# IoT-Main_Board.net
KiCad netlist of a schematic drawn in EasyEDA
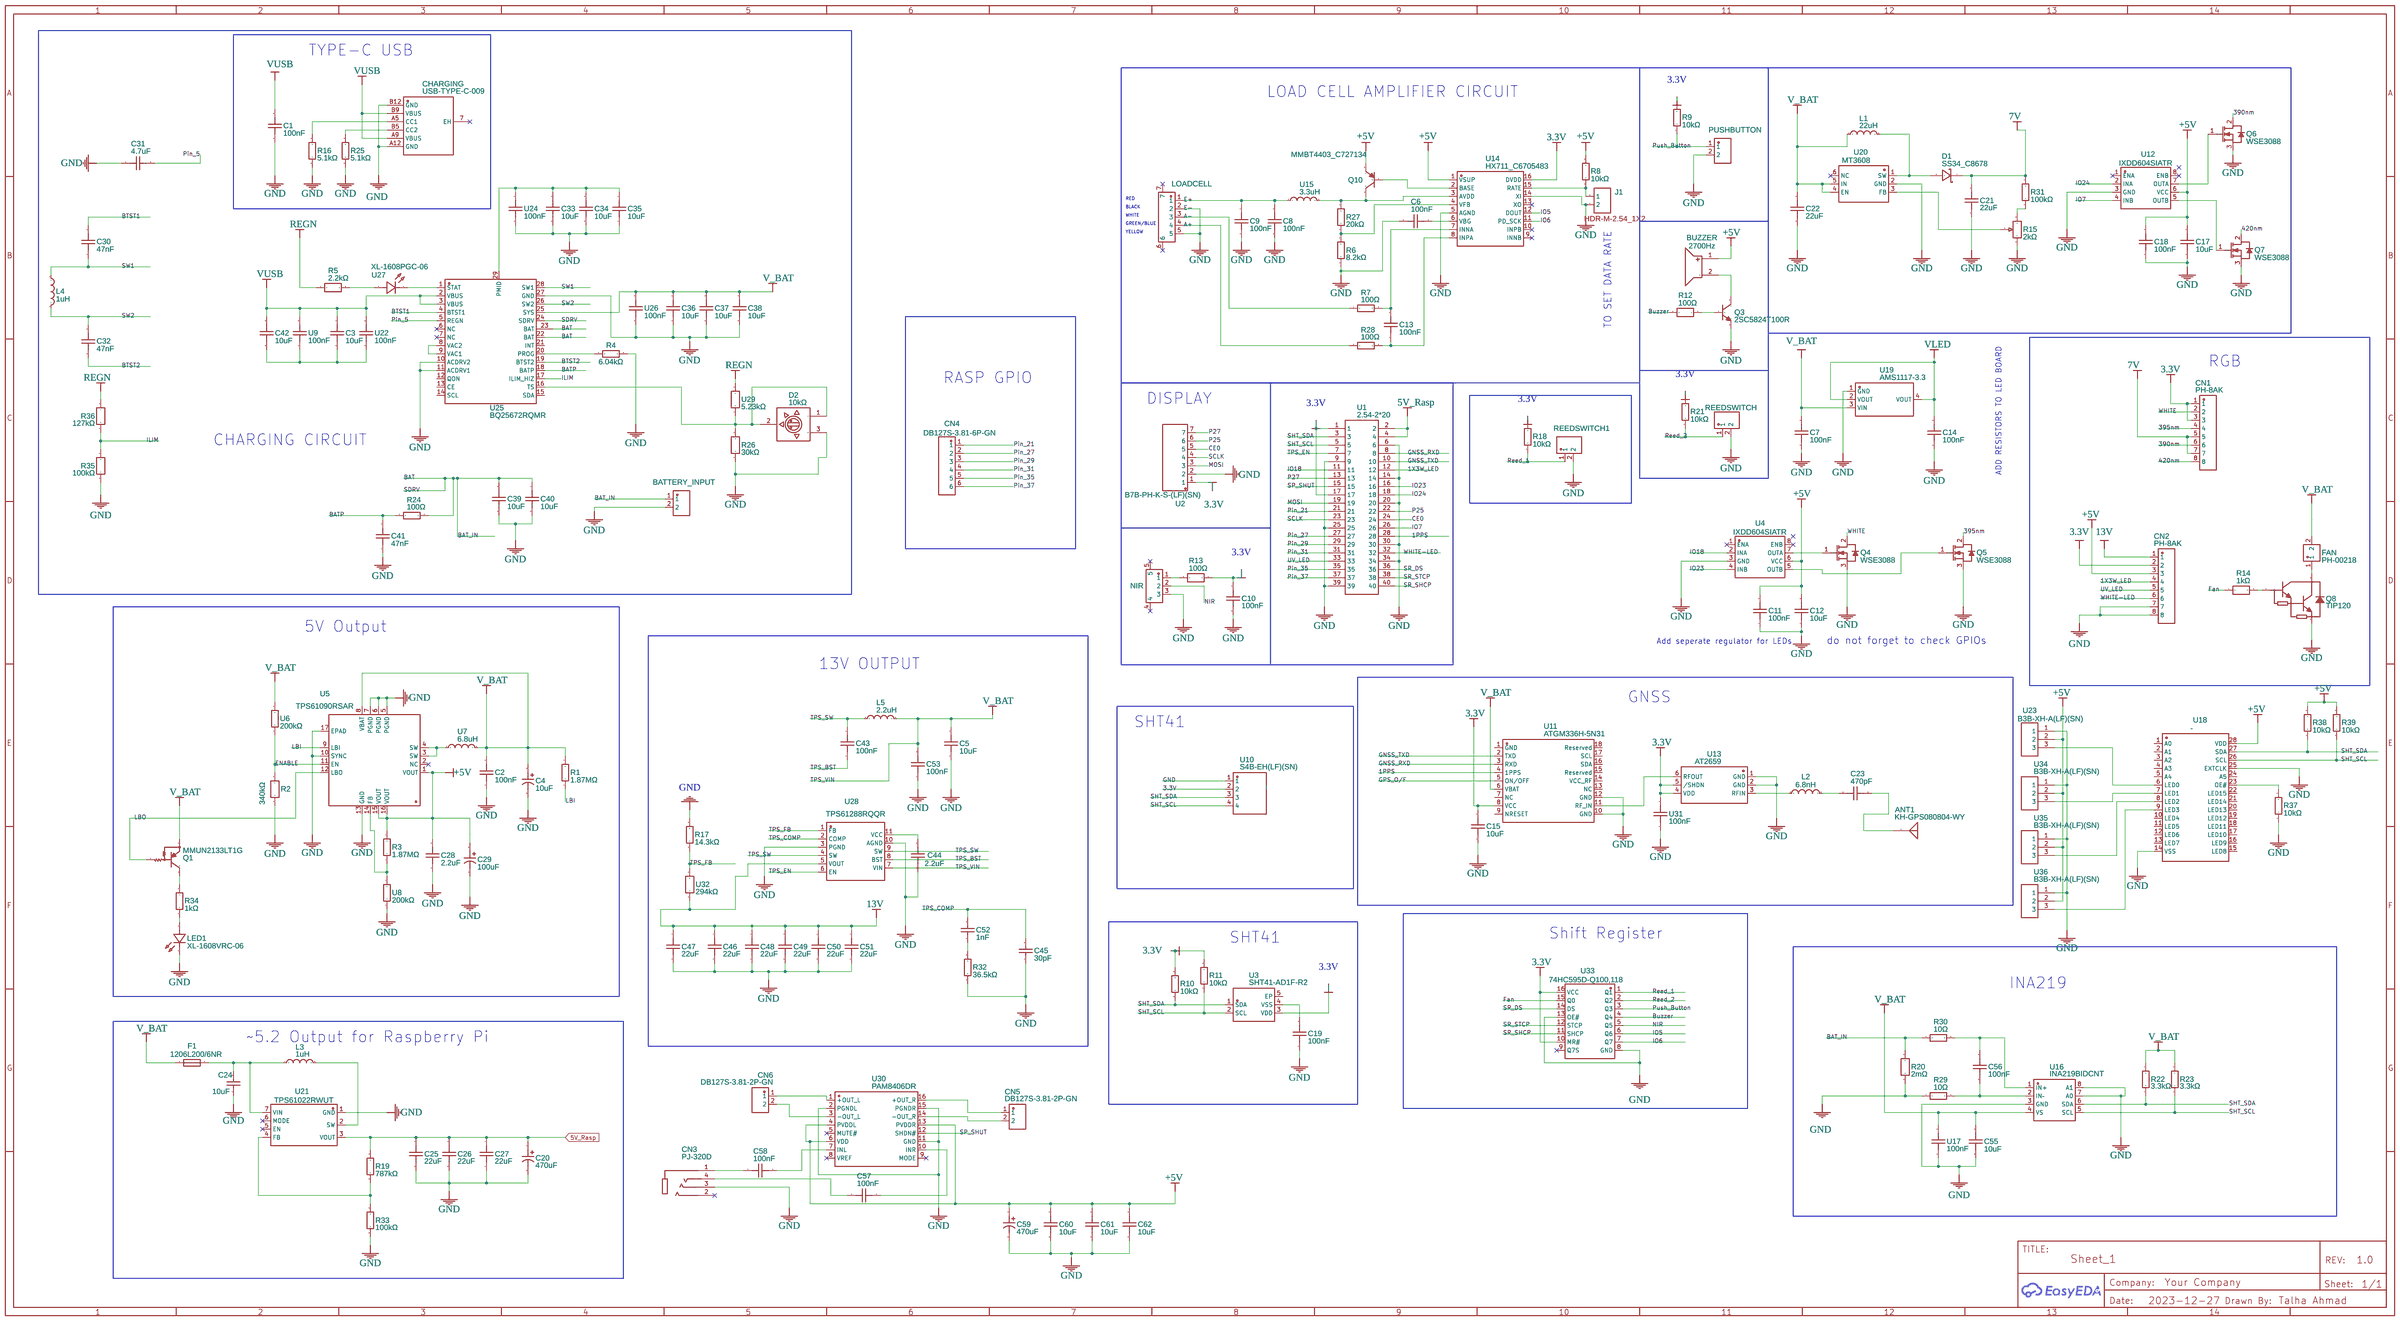
[diagram p0: schematic sheet]

(export (version "E")
  (design (tool "Eeschema 10.0.6"))
  (components
    (comp (ref "ANT1")
      (value "KH-GPS080804-WY")
      (fields (field (name "Manufacturer") "kinghelm(金航标)"))
      (libsource (lib "") (part "KH-GPS080804-WY"))
    )
    (comp (ref "BATTERY_INPUT")
      (value "PH-2A_C722767")
      (fields (field (name "Manufacturer Part") "PH-2A") (field (name "Manufacturer") "CAX(创都)"))
      (libsource (lib "") (part "PH-2A_C722767"))
    )
    (comp (ref "BUZZER")
      (value "2700Hz")
      (fields (field (name "Manufacturer Part") "QMB-09B-03") (field (name "Manufacturer") "华能"))
      (libsource (lib "") (part "QMB-09B-03"))
    )
    (comp (ref "C1")
      (value "100nF")
      (fields (field (name "Manufacturer Part") "C0603B104K500NT") (field (name "Manufacturer") "TORCH(火炬)"))
      (libsource (lib "") (part "C0603B104K500NT_1"))
    )
    (comp (ref "C2")
      (value "100nF")
      (fields (field (name "Manufacturer Part") "C0603B104K500NT") (field (name "Manufacturer") "TORCH(火炬)"))
      (libsource (lib "") (part "C0603B104K500NT_1"))
    )
    (comp (ref "C3")
      (value "10uF")
      (fields
        (field (name "Manufacturer Part") "CL10A106KO8NQNC")
        (field (name "Manufacturer") "SAMSUNG(三星)")
      )
      (libsource (lib "") (part "CL10A106KO8NQNC"))
    )
    (comp (ref "C4")
      (value "10uF")
      (fields
        (field (name "Manufacturer Part") "EFVH025ADA100M0454")
        (field (name "Manufacturer") "FOLLON(富隆电子)")
      )
      (libsource (lib "") (part "EFVH025ADA100M0454"))
    )
    (comp (ref "C5")
      (value "10uF")
      (fields
        (field (name "Manufacturer Part") "CL10A106KO8NQNC")
        (field (name "Manufacturer") "SAMSUNG(三星)")
      )
      (libsource (lib "") (part "CL10A106KO8NQNC"))
    )
    (comp (ref "C6")
      (value "100nF")
      (fields (field (name "Manufacturer Part") "C0603B104K500NT") (field (name "Manufacturer") "TORCH(火炬)"))
      (libsource (lib "") (part "C0603B104K500NT"))
    )
    (comp (ref "C7")
      (value "100nF")
      (fields (field (name "Manufacturer Part") "C0603B104K500NT") (field (name "Manufacturer") "TORCH(火炬)"))
      (libsource (lib "") (part "C0603B104K500NT_1"))
    )
    (comp (ref "C8")
      (value "100nF")
      (fields (field (name "Manufacturer Part") "C0603B104K500NT") (field (name "Manufacturer") "TORCH(火炬)"))
      (libsource (lib "") (part "C0603B104K500NT_1"))
    )
    (comp (ref "C9")
      (value "100nF")
      (fields (field (name "Manufacturer Part") "C0603B104K500NT") (field (name "Manufacturer") "TORCH(火炬)"))
      (libsource (lib "") (part "C0603B104K500NT_1"))
    )
    (comp (ref "C10")
      (value "100nF")
      (fields (field (name "Manufacturer Part") "C0603B104K500NT") (field (name "Manufacturer") "TORCH(火炬)"))
      (libsource (lib "") (part "C0603B104K500NT_2"))
    )
    (comp (ref "C11")
      (value "100nF")
      (fields (field (name "Manufacturer Part") "C0603B104K500NT") (field (name "Manufacturer") "TORCH(火炬)"))
      (libsource (lib "") (part "C0603B104K500NT_1"))
    )
    (comp (ref "C12")
      (value "10uF")
      (fields
        (field (name "Manufacturer Part") "CL10A106MA8NRNC")
        (field (name "Manufacturer") "SAMSUNG(三星)")
      )
      (libsource (lib "") (part "CL10A106MA8NRNC"))
    )
    (comp (ref "C13")
      (value "100nF")
      (fields (field (name "Manufacturer Part") "C0603B104K500NT") (field (name "Manufacturer") "TORCH(火炬)"))
      (libsource (lib "") (part "C0603B104K500NT_1"))
    )
    (comp (ref "C14")
      (value "100nF")
      (fields (field (name "Manufacturer Part") "C0603B104K500NT") (field (name "Manufacturer") "TORCH(火炬)"))
      (libsource (lib "") (part "C0603B104K500NT_1"))
    )
    (comp (ref "C15")
      (value "10uF")
      (fields
        (field (name "Manufacturer Part") "CL10A106KO8NQNC")
        (field (name "Manufacturer") "SAMSUNG(三星)")
      )
      (libsource (lib "") (part "CL10A106KO8NQNC_1"))
    )
    (comp (ref "C17")
      (value "10uF")
      (fields
        (field (name "Manufacturer Part") "CL10A106MA8NRNC")
        (field (name "Manufacturer") "SAMSUNG(三星)")
      )
      (libsource (lib "") (part "CL10A106MA8NRNC"))
    )
    (comp (ref "C18")
      (value "100nF")
      (fields (field (name "Manufacturer Part") "C0603B104K500NT") (field (name "Manufacturer") "TORCH(火炬)"))
      (libsource (lib "") (part "C0603B104K500NT_1"))
    )
    (comp (ref "C19")
      (value "100nF")
      (fields (field (name "Manufacturer Part") "C0603B104K500NT") (field (name "Manufacturer") "TORCH(火炬)"))
      (libsource (lib "") (part "C0603B104K500NT_1"))
    )
    (comp (ref "C20")
      (value "470uF")
      (fields (field (name "Manufacturer Part") "RVE1A471M0605") (field (name "Manufacturer") "ROQANG(容强)"))
      (libsource (lib "") (part "RVE1A471M0605_1"))
    )
    (comp (ref "C21")
      (value "22uF")
      (fields
        (field (name "Manufacturer Part") "CGA0805X5R226M350MT")
        (field (name "Manufacturer") "HRE(芯声)")
      )
      (libsource (lib "") (part "CGA0805X5R226M350MT"))
    )
    (comp (ref "C22")
      (value "22uF")
      (fields
        (field (name "Manufacturer Part") "CGA0805X5R226M350MT")
        (field (name "Manufacturer") "HRE(芯声)")
      )
      (libsource (lib "") (part "CGA0805X5R226M350MT"))
    )
    (comp (ref "C23")
      (value "470pF")
      (fields
        (field (name "Manufacturer Part") "CC0603KRX7R8BB471")
        (field (name "Manufacturer") "YAGEO(国巨)")
      )
      (libsource (lib "") (part "CC0603KRX7R8BB471"))
    )
    (comp (ref "C24")
      (value "10uF")
      (fields
        (field (name "Manufacturer Part") "CL10A106MO8NQNC")
        (field (name "Manufacturer") "SAMSUNG(三星)")
      )
      (libsource (lib "") (part "CL10A106MO8NQNC"))
    )
    (comp (ref "C25")
      (value "22uF")
      (fields
        (field (name "Manufacturer Part") "CL10A226MO7JZNC")
        (field (name "Manufacturer") "SAMSUNG(三星)")
      )
      (libsource (lib "") (part "CL10A226MO7JZNC"))
    )
    (comp (ref "C26")
      (value "22uF")
      (fields
        (field (name "Manufacturer Part") "CL10A226MO7JZNC")
        (field (name "Manufacturer") "SAMSUNG(三星)")
      )
      (libsource (lib "") (part "CL10A226MO7JZNC"))
    )
    (comp (ref "C27")
      (value "22uF")
      (fields
        (field (name "Manufacturer Part") "CL10A226MO7JZNC")
        (field (name "Manufacturer") "SAMSUNG(三星)")
      )
      (libsource (lib "") (part "CL10A226MO7JZNC"))
    )
    (comp (ref "C28")
      (value "2.2uF")
      (fields
        (field (name "Manufacturer Part") "GRM155R61E225KE11D")
        (field (name "Manufacturer") "muRata(村田)")
      )
      (libsource (lib "") (part "GRM155R61E225KE11D"))
    )
    (comp (ref "C29")
      (value "100uF")
      (fields
        (field (name "Manufacturer Part") "FVM025ADA101M0654")
        (field (name "Manufacturer") "FOSAN(富信)")
      )
      (libsource (lib "") (part "FVM025ADA101M0654"))
    )
    (comp (ref "C30")
      (value "47nF")
      (fields
        (field (name "Manufacturer Part") "TCC0603X7R473M500CT")
        (field (name "Manufacturer") "CCTC(三环)")
      )
      (libsource (lib "") (part "TCC0603X7R473M500CT"))
    )
    (comp (ref "C31")
      (value "4.7uF")
      (fields
        (field (name "Manufacturer Part") "TCC0603X5R475M250CT")
        (field (name "Manufacturer") "CCTC(三环)")
      )
      (libsource (lib "") (part "TCC0603X5R475M250CT"))
    )
    (comp (ref "C32")
      (value "47nF")
      (fields
        (field (name "Manufacturer Part") "TCC0603X7R473M500CT")
        (field (name "Manufacturer") "CCTC(三环)")
      )
      (libsource (lib "") (part "TCC0603X7R473M500CT"))
    )
    (comp (ref "C33")
      (value "10uF")
      (fields
        (field (name "Manufacturer Part") "CL10A106KO8NQNC")
        (field (name "Manufacturer") "SAMSUNG(三星)")
      )
      (libsource (lib "") (part "CL10A106KO8NQNC"))
    )
    (comp (ref "C34")
      (value "10uF")
      (fields
        (field (name "Manufacturer Part") "CL10A106KO8NQNC")
        (field (name "Manufacturer") "SAMSUNG(三星)")
      )
      (libsource (lib "") (part "CL10A106KO8NQNC"))
    )
    (comp (ref "C35")
      (value "10uF")
      (fields
        (field (name "Manufacturer Part") "CL10A106KO8NQNC")
        (field (name "Manufacturer") "SAMSUNG(三星)")
      )
      (libsource (lib "") (part "CL10A106KO8NQNC"))
    )
    (comp (ref "C36")
      (value "10uF")
      (fields
        (field (name "Manufacturer Part") "CL10A106KO8NQNC")
        (field (name "Manufacturer") "SAMSUNG(三星)")
      )
      (libsource (lib "") (part "CL10A106KO8NQNC"))
    )
    (comp (ref "C37")
      (value "10uF")
      (fields
        (field (name "Manufacturer Part") "CL10A106KO8NQNC")
        (field (name "Manufacturer") "SAMSUNG(三星)")
      )
      (libsource (lib "") (part "CL10A106KO8NQNC"))
    )
    (comp (ref "C38")
      (value "10uF")
      (fields
        (field (name "Manufacturer Part") "CL10A106KO8NQNC")
        (field (name "Manufacturer") "SAMSUNG(三星)")
      )
      (libsource (lib "") (part "CL10A106KO8NQNC"))
    )
    (comp (ref "C39")
      (value "10uF")
      (fields
        (field (name "Manufacturer Part") "CL10A106KO8NQNC")
        (field (name "Manufacturer") "SAMSUNG(三星)")
      )
      (libsource (lib "") (part "CL10A106KO8NQNC"))
    )
    (comp (ref "C40")
      (value "10uF")
      (fields
        (field (name "Manufacturer Part") "CL10A106KO8NQNC")
        (field (name "Manufacturer") "SAMSUNG(三星)")
      )
      (libsource (lib "") (part "CL10A106KO8NQNC"))
    )
    (comp (ref "C41")
      (value "47nF")
      (fields
        (field (name "Manufacturer Part") "TCC0603X7R473M500CT")
        (field (name "Manufacturer") "CCTC(三环)")
      )
      (libsource (lib "") (part "TCC0603X7R473M500CT"))
    )
    (comp (ref "C42")
      (value "10uF")
      (fields
        (field (name "Manufacturer Part") "CL10A106KO8NQNC")
        (field (name "Manufacturer") "SAMSUNG(三星)")
      )
      (libsource (lib "") (part "CL10A106KO8NQNC"))
    )
    (comp (ref "C43")
      (value "100nF")
      (fields (field (name "Manufacturer Part") "C0603B104K500NT") (field (name "Manufacturer") "TORCH(火炬)"))
      (libsource (lib "") (part "C0603B104K500NT_1"))
    )
    (comp (ref "C44")
      (value "2.2uF")
      (fields
        (field (name "Manufacturer Part") "EMK105ABJ225KV-F")
        (field (name "Manufacturer") "TAIYO YUDEN(太诱)")
      )
      (libsource (lib "") (part "EMK105ABJ225KV-F"))
    )
    (comp (ref "C45")
      (value "30pF")
      (fields
        (field (name "Manufacturer Part") "CC0402JRNPO9BN300")
        (field (name "Manufacturer") "YAGEO(国巨)")
      )
      (libsource (lib "") (part "CC0402JRNPO9BN300"))
    )
    (comp (ref "C46")
      (value "22uF")
      (fields
        (field (name "Manufacturer Part") "CL10A226MO7JZNC")
        (field (name "Manufacturer") "SAMSUNG(三星)")
      )
      (libsource (lib "") (part "CL10A226MO7JZNC"))
    )
    (comp (ref "C47")
      (value "22uF")
      (fields
        (field (name "Manufacturer Part") "CL10A226MO7JZNC")
        (field (name "Manufacturer") "SAMSUNG(三星)")
      )
      (libsource (lib "") (part "CL10A226MO7JZNC"))
    )
    (comp (ref "C48")
      (value "22uF")
      (fields
        (field (name "Manufacturer Part") "CL10A226MO7JZNC")
        (field (name "Manufacturer") "SAMSUNG(三星)")
      )
      (libsource (lib "") (part "CL10A226MO7JZNC"))
    )
    (comp (ref "C49")
      (value "22uF")
      (fields
        (field (name "Manufacturer Part") "CL10A226MO7JZNC")
        (field (name "Manufacturer") "SAMSUNG(三星)")
      )
      (libsource (lib "") (part "CL10A226MO7JZNC"))
    )
    (comp (ref "C50")
      (value "22uF")
      (fields
        (field (name "Manufacturer Part") "CL10A226MO7JZNC")
        (field (name "Manufacturer") "SAMSUNG(三星)")
      )
      (libsource (lib "") (part "CL10A226MO7JZNC"))
    )
    (comp (ref "C51")
      (value "22uF")
      (fields
        (field (name "Manufacturer Part") "CL10A226MO7JZNC")
        (field (name "Manufacturer") "SAMSUNG(三星)")
      )
      (libsource (lib "") (part "CL10A226MO7JZNC"))
    )
    (comp (ref "C52")
      (value "1nF")
      (fields
        (field (name "Manufacturer Part") "CC0402KRX7R9BB102")
        (field (name "Manufacturer") "YAGEO(国巨)")
      )
      (libsource (lib "") (part "CC0402KRX7R9BB102"))
    )
    (comp (ref "C53")
      (value "100nF")
      (fields (field (name "Manufacturer Part") "C0603B104K500NT") (field (name "Manufacturer") "TORCH(火炬)"))
      (libsource (lib "") (part "C0603B104K500NT_1"))
    )
    (comp (ref "C55")
      (value "10uF")
      (fields
        (field (name "Manufacturer Part") "CL10A106KO8NQNC")
        (field (name "Manufacturer") "SAMSUNG(三星)")
      )
      (libsource (lib "") (part "CL10A106KO8NQNC"))
    )
    (comp (ref "C56")
      (value "100nF")
      (fields (field (name "Manufacturer Part") "C0603B104K500NT") (field (name "Manufacturer") "TORCH(火炬)"))
      (libsource (lib "") (part "C0603B104K500NT_2"))
    )
    (comp (ref "C57")
      (value "100nF")
      (fields (field (name "Manufacturer Part") "C0603B104K500NT") (field (name "Manufacturer") "TORCH(火炬)"))
      (libsource (lib "") (part "C0603B104K500NT"))
    )
    (comp (ref "C58")
      (value "100nF")
      (fields (field (name "Manufacturer Part") "C0603B104K500NT") (field (name "Manufacturer") "TORCH(火炬)"))
      (libsource (lib "") (part "C0603B104K500NT"))
    )
    (comp (ref "C59")
      (value "470uF")
      (fields (field (name "Manufacturer Part") "RVE1A471M0605") (field (name "Manufacturer") "ROQANG(容强)"))
      (libsource (lib "") (part "RVE1A471M0605"))
    )
    (comp (ref "C60")
      (value "10uF")
      (fields
        (field (name "Manufacturer Part") "CL10A106KO8NQNC")
        (field (name "Manufacturer") "SAMSUNG(三星)")
      )
      (libsource (lib "") (part "CL10A106KO8NQNC"))
    )
    (comp (ref "C61")
      (value "10uF")
      (fields
        (field (name "Manufacturer Part") "CL10A106KO8NQNC")
        (field (name "Manufacturer") "SAMSUNG(三星)")
      )
      (libsource (lib "") (part "CL10A106KO8NQNC"))
    )
    (comp (ref "C62")
      (value "10uF")
      (fields
        (field (name "Manufacturer Part") "CL10A106KO8NQNC")
        (field (name "Manufacturer") "SAMSUNG(三星)")
      )
      (libsource (lib "") (part "CL10A106KO8NQNC"))
    )
    (comp (ref "CHARGING")
      (value "USB-TYPE-C-009")
      (fields (field (name "Manufacturer") "DEALON(德艺隆)"))
      (libsource (lib "") (part "USB-TYPE-C-009"))
    )
    (comp (ref "CN1")
      (value "PH-8AK")
      (fields (field (name "Manufacturer") "BOOMELE(博穆精密)"))
      (libsource (lib "") (part "PH-8AK"))
    )
    (comp (ref "CN2")
      (value "PH-8AK")
      (fields (field (name "Manufacturer") "BOOMELE(博穆精密)"))
      (libsource (lib "") (part "PH-8AK"))
    )
    (comp (ref "CN3")
      (value "PJ-320D")
      (fields (field (name "Manufacturer") "SHOU HAN(首韩)"))
      (libsource (lib "") (part "PJ-320D"))
    )
    (comp (ref "CN4")
      (value "DB127S-3.81-6P-GN")
      (fields
        (field (name "Manufacturer Part") "DB127S-3.81-6P-GN-S")
        (field (name "Manufacturer") "DORABO(地博电气)")
      )
      (libsource (lib "") (part "DB127S-3.81-6P-GN"))
    )
    (comp (ref "CN5")
      (value "DB127S-3.81-2P-GN")
      (fields
        (field (name "Manufacturer Part") "DB127S-3.81-2P-GN-S")
        (field (name "Manufacturer") "DORABO(地博电气)")
      )
      (libsource (lib "") (part "DB127S-3.81-2P-GN"))
    )
    (comp (ref "CN6")
      (value "DB127S-3.81-2P-GN")
      (fields
        (field (name "Manufacturer Part") "DB127S-3.81-2P-GN-S")
        (field (name "Manufacturer") "DORABO(地博电气)")
      )
      (libsource (lib "") (part "DB127S-3.81-2P-GN_1"))
    )
    (comp (ref "D1")
      (value "SS34_C8678")
      (fields (field (name "Manufacturer Part") "SS34") (field (name "Manufacturer") "MDD"))
      (libsource (lib "") (part "SS34_C8678"))
    )
    (comp (ref "D2")
      (value "10kΩ")
      (fields (field (name "Manufacturer Part") "3314G-1-103E") (field (name "Manufacturer") "BOURNS"))
      (libsource (lib "") (part "3314G-1-103E"))
    )
    (comp (ref "F1")
      (value "1206L200/6NR")
      (fields (field (name "Manufacturer") "LUTE(陆特)"))
      (libsource (lib "") (part "1206L200/6NR"))
    )
    (comp (ref "FAN")
      (value "PH-00218")
      (fields (field (name "Manufacturer") "Liansheng(连盛)"))
      (libsource (lib "") (part "PH-00218"))
    )
    (comp (ref "J1") (value "HDR-M-2.54_1x2") (libsource (lib "") (part "HDR-M-2.54_1x2")))
    (comp (ref "L1")
      (value "22uH")
      (fields
        (field (name "Manufacturer Part") "PNLS6045-220M 22UH")
        (field (name "Manufacturer") "DMBJ(振宝佳)")
      )
      (libsource (lib "") (part "PNLS6045-220M 22UH"))
    )
    (comp (ref "L2")
      (value "6.8nH")
      (fields
        (field (name "Manufacturer Part") "CMCC1608C6N8JSP")
        (field (name "Manufacturer") "Cybermax(思博科技)")
      )
      (libsource (lib "") (part "CMCC1608C6N8JSP"))
    )
    (comp (ref "L3")
      (value "1uH")
      (fields (field (name "Manufacturer Part") "MLZ1005M1R0WT000") (field (name "Manufacturer") "TDK"))
      (libsource (lib "") (part "MLZ1005M1R0WT000_1"))
    )
    (comp (ref "L4")
      (value "1uH")
      (fields (field (name "Manufacturer Part") "MLZ1005M1R0WT000") (field (name "Manufacturer") "TDK"))
      (libsource (lib "") (part "MLZ1005M1R0WT000"))
    )
    (comp (ref "L5")
      (value "2.2uH")
      (fields (field (name "Manufacturer Part") "MLZ1608N2R2LT000") (field (name "Manufacturer") "TDK"))
      (libsource (lib "") (part "MLZ1608N2R2LT000"))
    )
    (comp (ref "LED1")
      (value "XL-1608VRC-06")
      (fields (field (name "Manufacturer") "XINGLIGHT(成兴光)"))
      (libsource (lib "") (part "XL-1608VRC-06"))
    )
    (comp (ref "LOADCELL")
      (value "HC-FPC-05-10-5RLTAG")
      (fields (field (name "Manufacturer") "HCTL(华灿天禄)"))
      (libsource (lib "") (part "HC-FPC-05-10-5RLTAG"))
    )
    (comp (ref "NIR")
      (value "1.0K-LS-3PWB")
      (fields (field (name "Manufacturer") "HDGC(华德共创)"))
      (libsource (lib "") (part "1.0K-LS-3PWB"))
    )
    (comp (ref "PUSHBUTTON")
      (value "PH-2A_C722767")
      (fields (field (name "Manufacturer Part") "PH-2A") (field (name "Manufacturer") "CAX(创都)"))
      (libsource (lib "") (part "PH-2A_C722767_2"))
    )
    (comp (ref "Q1")
      (value "MMUN2133LT1G")
      (fields (field (name "Manufacturer") "onsemi(安森美)"))
      (libsource (lib "") (part "MMUN2133LT1G"))
    )
    (comp (ref "Q3")
      (value "2SC5824T100R")
      (fields (field (name "Manufacturer") "ROHM(罗姆)"))
      (libsource (lib "") (part "2SC5824T100R"))
    )
    (comp (ref "Q4")
      (value "WSE3088")
      (fields (field (name "Manufacturer") "WINSOK(微硕)"))
      (libsource (lib "") (part "WSE3088"))
    )
    (comp (ref "Q5")
      (value "WSE3088")
      (fields (field (name "Manufacturer") "WINSOK(微硕)"))
      (libsource (lib "") (part "WSE3088"))
    )
    (comp (ref "Q6")
      (value "WSE3088")
      (fields (field (name "Manufacturer") "WINSOK(微硕)"))
      (libsource (lib "") (part "WSE3088"))
    )
    (comp (ref "Q7")
      (value "WSE3088")
      (fields (field (name "Manufacturer") "WINSOK(微硕)"))
      (libsource (lib "") (part "WSE3088"))
    )
    (comp (ref "Q8")
      (value "TIP120")
      (fields (field (name "Manufacturer") "CJ(江苏长电/长晶)"))
      (libsource (lib "") (part "TIP120_C2992069"))
    )
    (comp (ref "Q10")
      (value "MMBT4403_C727134")
      (fields (field (name "Manufacturer Part") "MMBT4403") (field (name "Manufacturer") "TWGMC(台湾迪嘉)"))
      (libsource (lib "") (part "MMBT4403_C727134"))
    )
    (comp (ref "R1")
      (value "1.87MΩ")
      (fields
        (field (name "Manufacturer Part") "0603WAF1874T5E")
        (field (name "Manufacturer") "UNI-ROYAL(厚声)")
      )
      (libsource (lib "") (part "0603WAF1874T5E"))
    )
    (comp (ref "R2")
      (value "340kΩ")
      (fields (field (name "Manufacturer Part") "RC0402FR-07340KL") (field (name "Manufacturer") "YAGEO(国巨)"))
      (libsource (lib "") (part "RC0402FR-07340KL"))
    )
    (comp (ref "R3")
      (value "1.87MΩ")
      (fields
        (field (name "Manufacturer Part") "0603WAF1874T5E")
        (field (name "Manufacturer") "UNI-ROYAL(厚声)")
      )
      (libsource (lib "") (part "0603WAF1874T5E"))
    )
    (comp (ref "R4")
      (value "6.04kΩ")
      (fields (field (name "Manufacturer Part") "RC0402FR-076K04L") (field (name "Manufacturer") "YAGEO(国巨)"))
      (libsource (lib "") (part "RC0402FR-076K04L"))
    )
    (comp (ref "R5")
      (value "2.2kΩ")
      (fields (field (name "Manufacturer Part") "ERJUP3J222V") (field (name "Manufacturer") "PANASONIC(松下)"))
      (libsource (lib "") (part "ERJUP3J222V"))
    )
    (comp (ref "R6")
      (value "8.2kΩ")
      (fields (field (name "Manufacturer Part") "RC0805JR-078K2L") (field (name "Manufacturer") "YAGEO(国巨)"))
      (libsource (lib "") (part "RC0805JR-078K2L"))
    )
    (comp (ref "R7")
      (value "100Ω")
      (fields (field (name "Manufacturer Part") "ESR03EZPJ101") (field (name "Manufacturer") "ROHM(罗姆)"))
      (libsource (lib "") (part "ESR03EZPJ101"))
    )
    (comp (ref "R8")
      (value "10kΩ")
      (fields (field (name "Manufacturer Part") "ERA3AEB103V") (field (name "Manufacturer") "PANASONIC(松下)"))
      (libsource (lib "") (part "ERA-3AEB103V"))
    )
    (comp (ref "R9")
      (value "10kΩ")
      (fields (field (name "Manufacturer Part") "ERA3AEB103V") (field (name "Manufacturer") "PANASONIC(松下)"))
      (libsource (lib "") (part "ERA-3AEB103V"))
    )
    (comp (ref "R10")
      (value "10kΩ")
      (fields (field (name "Manufacturer Part") "ERA3AEB103V") (field (name "Manufacturer") "PANASONIC(松下)"))
      (libsource (lib "") (part "ERA-3AEB103V"))
    )
    (comp (ref "R11")
      (value "10kΩ")
      (fields (field (name "Manufacturer Part") "ERA3AEB103V") (field (name "Manufacturer") "PANASONIC(松下)"))
      (libsource (lib "") (part "ERA-3AEB103V"))
    )
    (comp (ref "R12")
      (value "100Ω")
      (fields (field (name "Manufacturer Part") "ERJP03F1000V") (field (name "Manufacturer") "PANASONIC(松下)"))
      (libsource (lib "") (part "ERJP03F1000V"))
    )
    (comp (ref "R13")
      (value "100Ω")
      (fields (field (name "Manufacturer Part") "ERJP03F1000V") (field (name "Manufacturer") "PANASONIC(松下)"))
      (libsource (lib "") (part "ERJP03F1000V"))
    )
    (comp (ref "R14")
      (value "1kΩ")
      (fields (field (name "Manufacturer Part") "ERJUP3F1001V") (field (name "Manufacturer") "PANASONIC(松下)"))
      (libsource (lib "") (part "ERJUP3F1001V"))
    )
    (comp (ref "R15")
      (value "2kΩ")
      (fields (field (name "Manufacturer Part") "3362P-1-202") (field (name "Manufacturer") "BOCHEN(博晨)"))
      (libsource (lib "") (part "3362P-1-202_C118929"))
    )
    (comp (ref "R16")
      (value "5.1kΩ")
      (fields (field (name "Manufacturer Part") "RC1206JR-075K1L") (field (name "Manufacturer") "YAGEO(国巨)"))
      (libsource (lib "") (part "RC1206JR-075K1L"))
    )
    (comp (ref "R17")
      (value "14.3kΩ")
      (fields (field (name "Manufacturer Part") "RK73H1ETTP1432F") (field (name "Manufacturer") "KOA"))
      (libsource (lib "") (part "RK73H1ETTP1432F"))
    )
    (comp (ref "R18")
      (value "10kΩ")
      (fields (field (name "Manufacturer Part") "ERA3AEB103V") (field (name "Manufacturer") "PANASONIC(松下)"))
      (libsource (lib "") (part "ERA-3AEB103V"))
    )
    (comp (ref "R19")
      (value "787kΩ")
      (fields
        (field (name "Manufacturer Part") "CR0603F787KP05Z")
        (field (name "Manufacturer") "EVER OHMS(天二科技)")
      )
      (libsource (lib "") (part "CR0603F787KP05"))
    )
    (comp (ref "R20")
      (value "2mΩ")
      (fields
        (field (name "Manufacturer Part") "HoLLR2512-3W-2mR-1%")
        (field (name "Manufacturer") "Milliohm(毫欧)")
      )
      (libsource (lib "") (part "HOLLR2512-3W-2MR-1%"))
    )
    (comp (ref "R21")
      (value "10kΩ")
      (fields (field (name "Manufacturer Part") "ERA3AEB103V") (field (name "Manufacturer") "PANASONIC(松下)"))
      (libsource (lib "") (part "ERA-3AEB103V"))
    )
    (comp (ref "R22")
      (value "3.3kΩ")
      (fields (field (name "Manufacturer Part") "RC0402FR-073K3L") (field (name "Manufacturer") "YAGEO(国巨)"))
      (libsource (lib "") (part "RC0402FR-073K3L"))
    )
    (comp (ref "R23")
      (value "3.3kΩ")
      (fields (field (name "Manufacturer Part") "RC0402FR-073K3L") (field (name "Manufacturer") "YAGEO(国巨)"))
      (libsource (lib "") (part "RC0402FR-073K3L"))
    )
    (comp (ref "R24")
      (value "100Ω")
      (fields (field (name "Manufacturer Part") "ESR03EZPJ101") (field (name "Manufacturer") "ROHM(罗姆)"))
      (libsource (lib "") (part "ESR03EZPJ101"))
    )
    (comp (ref "R25")
      (value "5.1kΩ")
      (fields (field (name "Manufacturer Part") "RC1206JR-075K1L") (field (name "Manufacturer") "YAGEO(国巨)"))
      (libsource (lib "") (part "RC1206JR-075K1L"))
    )
    (comp (ref "R26")
      (value "30kΩ")
      (fields (field (name "Manufacturer Part") "FRC0603F3002TS") (field (name "Manufacturer") "FOJAN(富捷)"))
      (libsource (lib "") (part "FRC0603F3002TS"))
    )
    (comp (ref "R27")
      (value "20kΩ")
      (fields (field (name "Manufacturer Part") "RC0805JR-0720KL") (field (name "Manufacturer") "YAGEO(国巨)"))
      (libsource (lib "") (part "RC0805JR-0720KL"))
    )
    (comp (ref "R28")
      (value "100Ω")
      (fields (field (name "Manufacturer Part") "ESR03EZPJ101") (field (name "Manufacturer") "ROHM(罗姆)"))
      (libsource (lib "") (part "ESR03EZPJ101"))
    )
    (comp (ref "R29")
      (value "10Ω")
      (fields (field (name "Manufacturer Part") "RC0402FR-0710RL") (field (name "Manufacturer") "YAGEO(国巨)"))
      (libsource (lib "") (part "RC0402FR-0710RL"))
    )
    (comp (ref "R30")
      (value "10Ω")
      (fields (field (name "Manufacturer Part") "RC0402FR-0710RL") (field (name "Manufacturer") "YAGEO(国巨)"))
      (libsource (lib "") (part "RC0402FR-0710RL"))
    )
    (comp (ref "R31")
      (value "100kΩ")
      (fields (field (name "Manufacturer Part") "ERJPB3D1003V") (field (name "Manufacturer") "PANASONIC(松下)"))
      (libsource (lib "") (part "ERJPB3D1003V"))
    )
    (comp (ref "R32")
      (value "36.5kΩ")
      (fields (field (name "Manufacturer Part") "RC0603FR-0736K5L") (field (name "Manufacturer") "YAGEO(国巨)"))
      (libsource (lib "") (part "RC0603FR-0736K5L"))
    )
    (comp (ref "R33")
      (value "100kΩ")
      (fields (field (name "Manufacturer Part") "RC0603FR-07100KL") (field (name "Manufacturer") "YAGEO(国巨)"))
      (libsource (lib "") (part "RC0603FR-07100KL"))
    )
    (comp (ref "R34")
      (value "1kΩ")
      (fields (field (name "Manufacturer Part") "ESR03EZPJ102") (field (name "Manufacturer") "ROHM(罗姆)"))
      (libsource (lib "") (part "ESR03EZPJ102"))
    )
    (comp (ref "R35")
      (value "100kΩ")
      (fields
        (field (name "Manufacturer Part") "CRCW0603100KFKEAHP")
        (field (name "Manufacturer") "VISHAY(威世)")
      )
      (libsource (lib "") (part "CRCW0603100KFKEAHP"))
    )
    (comp (ref "R36")
      (value "127kΩ")
      (fields (field (name "Manufacturer Part") "FRC0603F1273TS") (field (name "Manufacturer") "FOJAN(富捷)"))
      (libsource (lib "") (part "FRC0603F1273TS"))
    )
    (comp (ref "R37")
      (value "10kΩ")
      (fields (field (name "Manufacturer Part") "ERA3AEB103V") (field (name "Manufacturer") "PANASONIC(松下)"))
      (libsource (lib "") (part "ERA-3AEB103V"))
    )
    (comp (ref "R38")
      (value "10kΩ")
      (fields (field (name "Manufacturer Part") "ERA3AEB103V") (field (name "Manufacturer") "PANASONIC(松下)"))
      (libsource (lib "") (part "ERA-3AEB103V"))
    )
    (comp (ref "R39")
      (value "10kΩ")
      (fields (field (name "Manufacturer Part") "ERA3AEB103V") (field (name "Manufacturer") "PANASONIC(松下)"))
      (libsource (lib "") (part "ERA-3AEB103V"))
    )
    (comp (ref "REEDSWITCH")
      (value "PH-2A_C722767")
      (fields (field (name "Manufacturer Part") "PH-2A") (field (name "Manufacturer") "CAX(创都)"))
      (libsource (lib "") (part "PH-2A_C722767_1"))
    )
    (comp (ref "REEDSWITCH1")
      (value "PH-2A_C722767")
      (fields (field (name "Manufacturer Part") "PH-2A") (field (name "Manufacturer") "CAX(创都)"))
      (libsource (lib "") (part "PH-2A_C722767_1"))
    )
    (comp (ref "U1")
      (value "2.54-2*20")
      (fields (field (name "Manufacturer") "ZHOURI(洲日)"))
      (libsource (lib "") (part "2.54-2*20"))
    )
    (comp (ref "U2")
      (value "B7B-PH-K-S-(LF)(SN)")
      (fields (field (name "Manufacturer Part") "B7B-PH-K-S(LF)(SN)") (field (name "Manufacturer") "JST"))
      (libsource (lib "") (part "B7B-PH-K-S-(LF)(SN)"))
    )
    (comp (ref "U3")
      (value "SHT41-AD1F-R2")
      (fields (field (name "Manufacturer") "Sensirion(瑞士盛思锐)"))
      (libsource (lib "") (part "SHT41-AD1F-R2"))
    )
    (comp (ref "U4")
      (value "IXDD604SIATR")
      (fields (field (name "Manufacturer") "Littelfuse/IXYS"))
      (libsource (lib "") (part "IXDD604SIATR"))
    )
    (comp (ref "U5")
      (value "TPS61090RSAR")
      (fields (field (name "Manufacturer") "TI(德州仪器)"))
      (libsource (lib "") (part "TPS61090RSAR"))
    )
    (comp (ref "U6")
      (value "200kΩ")
      (fields (field (name "Manufacturer Part") "RTT052003FTP") (field (name "Manufacturer") "RALEC(旺诠)"))
      (libsource (lib "") (part "RTT052003FTP"))
    )
    (comp (ref "U7")
      (value "6.8uH")
      (fields (field (name "Manufacturer Part") "CY43-6.8UH") (field (name "Manufacturer") "SHOU HAN(首韩)"))
      (libsource (lib "") (part "CY43-6.8UH"))
    )
    (comp (ref "U8")
      (value "200kΩ")
      (fields (field (name "Manufacturer Part") "RTT052003FTP") (field (name "Manufacturer") "RALEC(旺诠)"))
      (libsource (lib "") (part "RTT052003FTP"))
    )
    (comp (ref "U9")
      (value "100nF")
      (fields
        (field (name "Manufacturer Part") "CL31B104KBCNFNC")
        (field (name "Manufacturer") "SAMSUNG(三星)")
      )
      (libsource (lib "") (part "CL31B104KBCNFNC"))
    )
    (comp (ref "U10")
      (value "S4B-EH(LF)(SN)")
      (fields (field (name "Manufacturer") "JST"))
      (libsource (lib "") (part "S4B-EH(LF)(SN)"))
    )
    (comp (ref "U11")
      (value "ATGM336H-5N31")
      (fields (field (name "Manufacturer") "杭州中科微"))
      (libsource (lib "") (part "ATGM336H-5N31"))
    )
    (comp (ref "U12")
      (value "IXDD604SIATR")
      (fields (field (name "Manufacturer") "Littelfuse/IXYS"))
      (libsource (lib "") (part "IXDD604SIATR"))
    )
    (comp (ref "U13")
      (value "AT2659")
      (fields (field (name "Manufacturer") "ZHONGKEWEI"))
      (libsource (lib "") (part "AT2659"))
    )
    (comp (ref "U14")
      (value "HX711_C6705483")
      (fields (field (name "Manufacturer Part") "HX711") (field (name "Manufacturer") "AVIA(海芯科技)"))
      (libsource (lib "") (part "HX711_C6705483"))
    )
    (comp (ref "U15")
      (value "3.3uH")
      (fields (field (name "Manufacturer Part") "CY54-3.3UH") (field (name "Manufacturer") "SHOU HAN(首韩)"))
      (libsource (lib "") (part "CY54-3.3UH"))
    )
    (comp (ref "U16")
      (value "INA219BIDCNT")
      (fields (field (name "Manufacturer") "TI(德州仪器)"))
      (libsource (lib "") (part "INA219BIDCNT"))
    )
    (comp (ref "U17")
      (value "100nF")
      (fields
        (field (name "Manufacturer Part") "CL31B104KBCNFNC")
        (field (name "Manufacturer") "SAMSUNG(三星)")
      )
      (libsource (lib "") (part "CL31B104KBCNFNC"))
    )
    (comp (ref "U18")
      (value "-")
      (fields
        (field (name "Manufacturer Part") "PCA9685PW/Q900,118")
        (field (name "Manufacturer") "NXP(恩智浦)")
      )
      (libsource (lib "") (part "PCA9685PW/Q900,118"))
    )
    (comp (ref "U19")
      (value "AMS1117-3.3")
      (fields (field (name "Manufacturer") "AMS"))
      (libsource (lib "") (part "AMS1117-3.3"))
    )
    (comp (ref "U20")
      (value "MT3608")
      (fields (field (name "Manufacturer") "西安航天民芯"))
      (libsource (lib "") (part "MT3608"))
    )
    (comp (ref "U21")
      (value "TPS61022RWUT")
      (fields (field (name "Manufacturer") "TI(德州仪器)"))
      (libsource (lib "") (part "TPS61022RWUT"))
    )
    (comp (ref "U22")
      (value "100nF")
      (fields
        (field (name "Manufacturer Part") "CL31B104KBCNFNC")
        (field (name "Manufacturer") "SAMSUNG(三星)")
      )
      (libsource (lib "") (part "CL31B104KBCNFNC"))
    )
    (comp (ref "U23")
      (value "B3B-XH-A(LF)(SN)")
      (fields (field (name "Manufacturer") "JST"))
      (libsource (lib "") (part "B3B-XH-A(LF)(SN)"))
    )
    (comp (ref "U24")
      (value "100nF")
      (fields
        (field (name "Manufacturer Part") "CL31B104KBCNFNC")
        (field (name "Manufacturer") "SAMSUNG(三星)")
      )
      (libsource (lib "") (part "CL31B104KBCNFNC"))
    )
    (comp (ref "U25")
      (value "BQ25672RQMR")
      (fields (field (name "Manufacturer") "TI(德州仪器)"))
      (libsource (lib "") (part "BQ25672RQMR"))
    )
    (comp (ref "U26")
      (value "100nF")
      (fields
        (field (name "Manufacturer Part") "CL31B104KBCNFNC")
        (field (name "Manufacturer") "SAMSUNG(三星)")
      )
      (libsource (lib "") (part "CL31B104KBCNFNC"))
    )
    (comp (ref "U27")
      (value "XL-1608PGC-06")
      (fields (field (name "Manufacturer") "XINGLIGHT(成兴光)"))
      (libsource (lib "") (part "XL-1608PGC-06"))
    )
    (comp (ref "U28")
      (value "TPS61288RQQR")
      (fields (field (name "Manufacturer") "TI(德州仪器)"))
      (libsource (lib "") (part "TPS61288RQQR"))
    )
    (comp (ref "U29")
      (value "5.23kΩ")
      (fields
        (field (name "Manufacturer Part") "CRCW04025K23FKED")
        (field (name "Manufacturer") "VISHAY(威世)")
      )
      (libsource (lib "") (part "CRCW04025K23FKED"))
    )
    (comp (ref "U30")
      (value "PAM8406DR")
      (fields (field (name "Manufacturer") "DIODES(美台)"))
      (libsource (lib "") (part "PAM8406DR"))
    )
    (comp (ref "U31")
      (value "100nF")
      (fields
        (field (name "Manufacturer Part") "CL31B104KBCNFNC")
        (field (name "Manufacturer") "SAMSUNG(三星)")
      )
      (libsource (lib "") (part "CL31B104KBCNFNC"))
    )
    (comp (ref "U32")
      (value "294kΩ")
      (fields (field (name "Manufacturer Part") "RT0603BRD07294KL") (field (name "Manufacturer") "YAGEO(国巨)"))
      (libsource (lib "") (part "RT0603BRD07294KL"))
    )
    (comp (ref "U33")
      (value "74HC595D-Q100,118")
      (fields (field (name "Manufacturer") "Nexperia(安世)"))
      (libsource (lib "") (part "74HC595D-Q100,118"))
    )
    (comp (ref "U34")
      (value "B3B-XH-A(LF)(SN)")
      (fields (field (name "Manufacturer") "JST"))
      (libsource (lib "") (part "B3B-XH-A(LF)(SN)"))
    )
    (comp (ref "U35")
      (value "B3B-XH-A(LF)(SN)")
      (fields (field (name "Manufacturer") "JST"))
      (libsource (lib "") (part "B3B-XH-A(LF)(SN)"))
    )
    (comp (ref "U36")
      (value "B3B-XH-A(LF)(SN)")
      (fields (field (name "Manufacturer") "JST"))
      (libsource (lib "") (part "B3B-XH-A(LF)(SN)"))
    )
  )
  (nets
    (net (code "1") (name "+5V") (class "Default")
      (node (ref "BUZZER") (pin "1") (pinfunction "1_1") (pintype "unspecified"))
      (node (ref "C11") (pin "2") (pinfunction "2_2") (pintype "unspecified"))
      (node (ref "C12") (pin "2") (pinfunction "2_2") (pintype "unspecified"))
      (node (ref "C17") (pin "2") (pinfunction "2_2") (pintype "unspecified"))
      (node (ref "C18") (pin "2") (pinfunction "2_2") (pintype "unspecified"))
      (node (ref "C28") (pin "2") (pinfunction "2_2") (pintype "unspecified"))
      (node (ref "C29") (pin "1") (pinfunction "1_1") (pintype "input"))
      (node (ref "C59") (pin "1") (pinfunction "1_1") (pintype "input"))
      (node (ref "C60") (pin "1") (pinfunction "1_1") (pintype "unspecified"))
      (node (ref "C61") (pin "1") (pinfunction "1_1") (pintype "unspecified"))
      (node (ref "C62") (pin "1") (pinfunction "1_1") (pintype "unspecified"))
      (node (ref "CN2") (pin "3") (pinfunction "3_3") (pintype "unspecified"))
      (node (ref "Q10") (pin "2") (pinfunction "E_2") (pintype "input"))
      (node (ref "R3") (pin "2") (pinfunction "2_2") (pintype "input"))
      (node (ref "R38") (pin "2") (pinfunction "2_2") (pintype "input"))
      (node (ref "R39") (pin "2") (pinfunction "2_2") (pintype "input"))
      (node (ref "R8") (pin "2") (pinfunction "2_2") (pintype "input"))
      (node (ref "U12") (pin "6") (pinfunction "VCC_6") (pintype "unspecified"))
      (node (ref "U14") (pin "1") (pinfunction "VSUP_1") (pintype "unspecified"))
      (node (ref "U18") (pin "28") (pinfunction "VDD_28") (pintype "unspecified"))
      (node (ref "U23") (pin "2") (pinfunction "2_2") (pintype "unspecified"))
      (node (ref "U30") (pin "13") (pinfunction "PVDDR_13") (pintype "unspecified"))
      (node (ref "U30") (pin "4") (pinfunction "PVDDL_4") (pintype "unspecified"))
      (node (ref "U30") (pin "6") (pinfunction "VDD_6") (pintype "unspecified"))
      (node (ref "U34") (pin "2") (pinfunction "2_2") (pintype "unspecified"))
      (node (ref "U35") (pin "2") (pinfunction "2_2") (pintype "unspecified"))
      (node (ref "U36") (pin "2") (pinfunction "2_2") (pintype "unspecified"))
      (node (ref "U4") (pin "6") (pinfunction "VCC_6") (pintype "unspecified"))
      (node (ref "U5") (pin "1") (pinfunction "VOUT_1") (pintype "unspecified"))
      (node (ref "U5") (pin "15") (pinfunction "VOUT_15") (pintype "unspecified"))
      (node (ref "U5") (pin "16") (pinfunction "VOUT_16") (pintype "unspecified"))
    )
    (net (code "2") (name "/1PPS") (class "Default")
      (node (ref "U1") (pin "28") (pinfunction "28_28") (pintype "unspecified"))
      (node (ref "U11") (pin "4") (pinfunction "1PPS_4") (pintype "unspecified"))
    )
    (net (code "3") (name "/1X3W_LED") (class "Default")
      (node (ref "CN2") (pin "4") (pinfunction "4_4") (pintype "unspecified"))
      (node (ref "U1") (pin "12") (pinfunction "12_12") (pintype "unspecified"))
    )
    (net (code "4") (name "/390nm") (class "Default")
      (node (ref "CN1") (pin "6") (pinfunction "6_6") (pintype "unspecified"))
      (node (ref "Q6") (pin "2") (pinfunction "D_2") (pintype "unspecified"))
    )
    (net (code "5") (name "/395nm") (class "Default")
      (node (ref "CN1") (pin "4") (pinfunction "4_4") (pintype "unspecified"))
      (node (ref "Q5") (pin "2") (pinfunction "D_2") (pintype "unspecified"))
    )
    (net (code "6") (name "/420nm") (class "Default")
      (node (ref "CN1") (pin "8") (pinfunction "8_8") (pintype "unspecified"))
      (node (ref "Q7") (pin "2") (pinfunction "D_2") (pintype "unspecified"))
    )
    (net (code "7") (name "/A+") (class "Default")
      (node (ref "LOADCELL") (pin "4") (pinfunction "4_4") (pintype "unspecified"))
      (node (ref "R28") (pin "1") (pinfunction "1_1") (pintype "unspecified"))
    )
    (net (code "8") (name "/A-") (class "Default")
      (node (ref "LOADCELL") (pin "3") (pinfunction "3_3") (pintype "unspecified"))
      (node (ref "R7") (pin "1") (pinfunction "1_1") (pintype "unspecified"))
    )
    (net (code "9") (name "/BAT") (class "Default")
      (node (ref "BATTERY_INPUT") (pin "1") (pinfunction "1_1") (pintype "unspecified"))
      (node (ref "C39") (pin "1") (pinfunction "1_1") (pintype "unspecified"))
      (node (ref "C40") (pin "1") (pinfunction "1_1") (pintype "unspecified"))
      (node (ref "R20") (pin "2") (pinfunction "2_2") (pintype "unspecified"))
      (node (ref "R24") (pin "2") (pinfunction "2_2") (pintype "unspecified"))
      (node (ref "R30") (pin "1") (pinfunction "1_1") (pintype "input"))
      (node (ref "U25") (pin "22") (pinfunction "BAT_22") (pintype "unspecified"))
      (node (ref "U25") (pin "23") (pinfunction "BAT_23") (pintype "unspecified"))
      (node (ref "U25") (pin "24") (pinfunction "SDRV_24") (pintype "unspecified"))
    )
    (net (code "10") (name "/BATP") (class "Default")
      (node (ref "C41") (pin "2") (pinfunction "2_2") (pintype "unspecified"))
      (node (ref "R24") (pin "1") (pinfunction "1_1") (pintype "unspecified"))
      (node (ref "U25") (pin "18") (pinfunction "BATP_18") (pintype "unspecified"))
    )
    (net (code "11") (name "/BTST1") (class "Default")
      (node (ref "C30") (pin "2") (pinfunction "2_2") (pintype "unspecified"))
      (node (ref "U25") (pin "4") (pinfunction "BTST1_4") (pintype "unspecified"))
    )
    (net (code "12") (name "/BTST2") (class "Default")
      (node (ref "C32") (pin "1") (pinfunction "1_1") (pintype "unspecified"))
      (node (ref "U25") (pin "19") (pinfunction "BTST2_19") (pintype "unspecified"))
    )
    (net (code "13") (name "/Buzzer") (class "Default")
      (node (ref "R12") (pin "2") (pinfunction "2_2") (pintype "unspecified"))
      (node (ref "U33") (pin "4") (pinfunction "Q4_4") (pintype "unspecified"))
    )
    (net (code "14") (name "/CE0") (class "Default")
      (node (ref "U1") (pin "24") (pinfunction "24_24") (pintype "unspecified"))
      (node (ref "U2") (pin "5") (pinfunction "5_5") (pintype "unspecified"))
    )
    (net (code "15") (name "/E+") (class "Default")
      (node (ref "C8") (pin "2") (pinfunction "2_2") (pintype "unspecified"))
      (node (ref "C9") (pin "2") (pinfunction "2_2") (pintype "unspecified"))
      (node (ref "LOADCELL") (pin "1") (pinfunction "1_1") (pintype "unspecified"))
      (node (ref "U15") (pin "1") (pinfunction "1_1") (pintype "unspecified"))
    )
    (net (code "16") (name "/ENABLE") (class "Default")
      (node (ref "R2") (pin "2") (pinfunction "2_2") (pintype "unspecified"))
      (node (ref "U5") (pin "11") (pinfunction "EN_11") (pintype "unspecified"))
      (node (ref "U6") (pin "1") (pinfunction "1_1") (pintype "input"))
    )
    (net (code "17") (name "/Fan") (class "Default")
      (node (ref "R14") (pin "1") (pinfunction "1_1") (pintype "unspecified"))
      (node (ref "U33") (pin "15") (pinfunction "Q0_15") (pintype "unspecified"))
    )
    (net (code "18") (name "/GNSS_RXD") (class "Default")
      (node (ref "U1") (pin "8") (pinfunction "8_8") (pintype "unspecified"))
      (node (ref "U11") (pin "3") (pinfunction "RXD_3") (pintype "unspecified"))
    )
    (net (code "19") (name "/GNSS_TXD") (class "Default")
      (node (ref "U1") (pin "10") (pinfunction "10_10") (pintype "unspecified"))
      (node (ref "U11") (pin "2") (pinfunction "TXD_2") (pintype "unspecified"))
    )
    (net (code "20") (name "/GPS_O{slash}F") (class "Default")
      (node (ref "U11") (pin "5") (pinfunction "ON/OFF_5") (pintype "unspecified"))
    )
    (net (code "21") (name "/ILIM") (class "Default")
      (node (ref "R35") (pin "2") (pinfunction "2_2") (pintype "unspecified"))
      (node (ref "R36") (pin "2") (pinfunction "2_2") (pintype "unspecified"))
      (node (ref "U25") (pin "17") (pinfunction "ILIM_HIZ_17") (pintype "unspecified"))
    )
    (net (code "22") (name "/IO5") (class "Default")
      (node (ref "U14") (pin "12") (pinfunction "DOUT_12") (pintype "unspecified"))
      (node (ref "U33") (pin "6") (pinfunction "Q6_6") (pintype "unspecified"))
    )
    (net (code "23") (name "/IO6") (class "Default")
      (node (ref "U14") (pin "11") (pinfunction "PD_SCK_11") (pintype "unspecified"))
      (node (ref "U33") (pin "7") (pinfunction "Q7_7") (pintype "unspecified"))
    )
    (net (code "24") (name "/IO7") (class "Default")
      (node (ref "U1") (pin "26") (pinfunction "26_26") (pintype "unspecified"))
      (node (ref "U12") (pin "4") (pinfunction "INB_4") (pintype "unspecified"))
    )
    (net (code "25") (name "/IO18") (class "Default")
      (node (ref "U1") (pin "11") (pinfunction "11_11") (pintype "unspecified"))
      (node (ref "U4") (pin "2") (pinfunction "INA_2") (pintype "unspecified"))
    )
    (net (code "26") (name "/IO23") (class "Default")
      (node (ref "U1") (pin "16") (pinfunction "16_16") (pintype "unspecified"))
      (node (ref "U4") (pin "4") (pinfunction "INB_4") (pintype "unspecified"))
    )
    (net (code "27") (name "/IO24") (class "Default")
      (node (ref "U1") (pin "18") (pinfunction "18_18") (pintype "unspecified"))
      (node (ref "U12") (pin "2") (pinfunction "INA_2") (pintype "unspecified"))
    )
    (net (code "28") (name "/LBI") (class "Default")
      (node (ref "R1") (pin "1") (pinfunction "1_1") (pintype "input"))
      (node (ref "U5") (pin "9") (pinfunction "LBI_9") (pintype "unspecified"))
    )
    (net (code "29") (name "/LBO") (class "Default")
      (node (ref "Q1") (pin "1") (pinfunction "B_1") (pintype "unspecified"))
      (node (ref "U5") (pin "12") (pinfunction "LBO_12") (pintype "unspecified"))
    )
    (net (code "30") (name "/MOSI") (class "Default")
      (node (ref "U1") (pin "19") (pinfunction "19_19") (pintype "unspecified"))
      (node (ref "U2") (pin "3") (pinfunction "3_3") (pintype "unspecified"))
    )
    (net (code "31") (name "/NIR") (class "Default")
      (node (ref "NIR") (pin "2") (pinfunction "2_2") (pintype "unspecified"))
      (node (ref "U33") (pin "5") (pinfunction "Q5_5") (pintype "unspecified"))
    )
    (net (code "32") (name "/P25") (class "Default")
      (node (ref "U1") (pin "22") (pinfunction "22_22") (pintype "unspecified"))
      (node (ref "U2") (pin "6") (pinfunction "6_6") (pintype "unspecified"))
    )
    (net (code "33") (name "/P27") (class "Default")
      (node (ref "U1") (pin "13") (pinfunction "13_13") (pintype "unspecified"))
      (node (ref "U2") (pin "7") (pinfunction "7_7") (pintype "unspecified"))
    )
    (net (code "34") (name "/Pin_5") (class "Default")
      (node (ref "C31") (pin "2") (pinfunction "2_2") (pintype "unspecified"))
      (node (ref "U25") (pin "5") (pinfunction "REGN_5") (pintype "unspecified"))
    )
    (net (code "35") (name "/Pin_21") (class "Default")
      (node (ref "CN4") (pin "1") (pinfunction "1_1") (pintype "unspecified"))
      (node (ref "U1") (pin "21") (pinfunction "21_21") (pintype "unspecified"))
    )
    (net (code "36") (name "/Pin_27") (class "Default")
      (node (ref "CN4") (pin "2") (pinfunction "2_2") (pintype "unspecified"))
      (node (ref "U1") (pin "27") (pinfunction "27_27") (pintype "unspecified"))
    )
    (net (code "37") (name "/Pin_29") (class "Default")
      (node (ref "CN4") (pin "3") (pinfunction "3_3") (pintype "unspecified"))
      (node (ref "U1") (pin "29") (pinfunction "29_29") (pintype "unspecified"))
    )
    (net (code "38") (name "/Pin_31") (class "Default")
      (node (ref "CN4") (pin "4") (pinfunction "4_4") (pintype "unspecified"))
      (node (ref "U1") (pin "31") (pinfunction "31_31") (pintype "unspecified"))
    )
    (net (code "39") (name "/Pin_35") (class "Default")
      (node (ref "CN4") (pin "5") (pinfunction "5_5") (pintype "unspecified"))
      (node (ref "U1") (pin "35") (pinfunction "35_35") (pintype "unspecified"))
    )
    (net (code "40") (name "/Pin_37") (class "Default")
      (node (ref "CN4") (pin "6") (pinfunction "6_6") (pintype "unspecified"))
      (node (ref "U1") (pin "37") (pinfunction "37_37") (pintype "unspecified"))
    )
    (net (code "41") (name "/Push_Button") (class "Default")
      (node (ref "PUSHBUTTON") (pin "1") (pinfunction "1_1") (pintype "unspecified"))
      (node (ref "R9") (pin "1") (pinfunction "1_1") (pintype "input"))
      (node (ref "U33") (pin "3") (pinfunction "Q3_3") (pintype "unspecified"))
    )
    (net (code "42") (name "/Reed_1") (class "Default")
      (node (ref "R18") (pin "1") (pinfunction "1_1") (pintype "input"))
      (node (ref "REEDSWITCH1") (pin "1") (pinfunction "1_1") (pintype "unspecified"))
      (node (ref "U33") (pin "1") (pinfunction "Q1_1") (pintype "unspecified"))
    )
    (net (code "43") (name "/Reed_2") (class "Default")
      (node (ref "R21") (pin "1") (pinfunction "1_1") (pintype "input"))
      (node (ref "REEDSWITCH") (pin "1") (pinfunction "1_1") (pintype "unspecified"))
      (node (ref "U33") (pin "2") (pinfunction "Q2_2") (pintype "unspecified"))
    )
    (net (code "44") (name "/SCLK") (class "Default")
      (node (ref "U1") (pin "23") (pinfunction "23_23") (pintype "unspecified"))
      (node (ref "U2") (pin "4") (pinfunction "4_4") (pintype "unspecified"))
    )
    (net (code "45") (name "/SHT_SCL") (class "Default")
      (node (ref "R11") (pin "1") (pinfunction "1_1") (pintype "input"))
      (node (ref "R23") (pin "1") (pinfunction "1_1") (pintype "input"))
      (node (ref "R39") (pin "1") (pinfunction "1_1") (pintype "input"))
      (node (ref "U1") (pin "5") (pinfunction "5_5") (pintype "unspecified"))
      (node (ref "U10") (pin "4") (pinfunction "4_4") (pintype "unspecified"))
      (node (ref "U16") (pin "5") (pinfunction "SCL_5") (pintype "unspecified"))
      (node (ref "U18") (pin "26") (pinfunction "SCL_26") (pintype "unspecified"))
      (node (ref "U3") (pin "2") (pinfunction "SCL_2") (pintype "unspecified"))
    )
    (net (code "46") (name "/SHT_SDA") (class "Default")
      (node (ref "R10") (pin "1") (pinfunction "1_1") (pintype "input"))
      (node (ref "R22") (pin "1") (pinfunction "1_1") (pintype "input"))
      (node (ref "R38") (pin "1") (pinfunction "1_1") (pintype "input"))
      (node (ref "U1") (pin "3") (pinfunction "3_3") (pintype "unspecified"))
      (node (ref "U10") (pin "3") (pinfunction "3_3") (pintype "unspecified"))
      (node (ref "U16") (pin "6") (pinfunction "SDA_6") (pintype "unspecified"))
      (node (ref "U18") (pin "27") (pinfunction "SDA_27") (pintype "unspecified"))
      (node (ref "U3") (pin "1") (pinfunction "SDA_1") (pintype "unspecified"))
    )
    (net (code "47") (name "/SP_SHUT") (class "Default")
      (node (ref "U1") (pin "15") (pinfunction "15_15") (pintype "unspecified"))
      (node (ref "U30") (pin "12") (pinfunction "SHDN#_12") (pintype "unspecified"))
    )
    (net (code "48") (name "/SR_DS") (class "Default")
      (node (ref "U1") (pin "36") (pinfunction "36_36") (pintype "unspecified"))
      (node (ref "U33") (pin "14") (pinfunction "DS_14") (pintype "unspecified"))
    )
    (net (code "49") (name "/SR_SHCP") (class "Default")
      (node (ref "U1") (pin "40") (pinfunction "40_40") (pintype "unspecified"))
      (node (ref "U33") (pin "11") (pinfunction "SHCP_11") (pintype "unspecified"))
    )
    (net (code "50") (name "/SR_STCP") (class "Default")
      (node (ref "U1") (pin "38") (pinfunction "38_38") (pintype "unspecified"))
      (node (ref "U33") (pin "12") (pinfunction "STCP_12") (pintype "unspecified"))
    )
    (net (code "51") (name "/SW1") (class "Default")
      (node (ref "C30") (pin "1") (pinfunction "1_1") (pintype "unspecified"))
      (node (ref "L4") (pin "1") (pinfunction "1_1") (pintype "unspecified"))
      (node (ref "U25") (pin "28") (pinfunction "SW1_28") (pintype "unspecified"))
    )
    (net (code "52") (name "/SW2") (class "Default")
      (node (ref "C32") (pin "2") (pinfunction "2_2") (pintype "unspecified"))
      (node (ref "L4") (pin "2") (pinfunction "2_2") (pintype "unspecified"))
      (node (ref "U25") (pin "26") (pinfunction "SW2_26") (pintype "unspecified"))
    )
    (net (code "53") (name "/TPS_BST") (class "Default")
      (node (ref "C43") (pin "1") (pinfunction "1_1") (pintype "unspecified"))
      (node (ref "U28") (pin "8") (pinfunction "BST_8") (pintype "unspecified"))
    )
    (net (code "54") (name "/TPS_COMP") (class "Default")
      (node (ref "C45") (pin "2") (pinfunction "2_2") (pintype "input"))
      (node (ref "C52") (pin "2") (pinfunction "2_2") (pintype "input"))
      (node (ref "U28") (pin "2") (pinfunction "COMP_2") (pintype "unspecified"))
    )
    (net (code "55") (name "/TPS_EN") (class "Default")
      (node (ref "U1") (pin "7") (pinfunction "7_7") (pintype "unspecified"))
      (node (ref "U28") (pin "6") (pinfunction "EN_6") (pintype "unspecified"))
    )
    (net (code "56") (name "/TPS_FB") (class "Default")
      (node (ref "R17") (pin "1") (pinfunction "1_1") (pintype "unspecified"))
      (node (ref "U28") (pin "1") (pinfunction "FB_1") (pintype "unspecified"))
      (node (ref "U32") (pin "2") (pinfunction "2_2") (pintype "unspecified"))
    )
    (net (code "57") (name "/TPS_SW") (class "Default")
      (node (ref "C43") (pin "2") (pinfunction "2_2") (pintype "unspecified"))
      (node (ref "L5") (pin "1") (pinfunction "1_1") (pintype "unspecified"))
      (node (ref "U28") (pin "4") (pinfunction "SW_4") (pintype "unspecified"))
      (node (ref "U28") (pin "9") (pinfunction "SW_9") (pintype "unspecified"))
    )
    (net (code "58") (name "/UV_LED") (class "Default")
      (node (ref "CN2") (pin "5") (pinfunction "5_5") (pintype "unspecified"))
      (node (ref "U1") (pin "33") (pinfunction "33_33") (pintype "unspecified"))
    )
    (net (code "59") (name "/WHITE") (class "Default")
      (node (ref "CN1") (pin "2") (pinfunction "2_2") (pintype "unspecified"))
      (node (ref "Q4") (pin "2") (pinfunction "D_2") (pintype "unspecified"))
    )
    (net (code "60") (name "/WHITE-LED") (class "Default")
      (node (ref "CN2") (pin "6") (pinfunction "6_6") (pintype "unspecified"))
      (node (ref "U1") (pin "32") (pinfunction "32_32") (pintype "unspecified"))
    )
    (net (code "61") (name "3.3V") (class "Default")
      (node (ref "C10") (pin "1") (pinfunction "1_1") (pintype "unspecified"))
      (node (ref "C15") (pin "2") (pinfunction "2_2") (pintype "unspecified"))
      (node (ref "CN1") (pin "1") (pinfunction "1_1") (pintype "unspecified"))
      (node (ref "CN1") (pin "3") (pinfunction "3_3") (pintype "unspecified"))
      (node (ref "CN2") (pin "2") (pinfunction "2_2") (pintype "unspecified"))
      (node (ref "R10") (pin "2") (pinfunction "2_2") (pintype "input"))
      (node (ref "R11") (pin "2") (pinfunction "2_2") (pintype "input"))
      (node (ref "R13") (pin "1") (pinfunction "1_1") (pintype "unspecified"))
      (node (ref "R18") (pin "2") (pinfunction "2_2") (pintype "input"))
      (node (ref "R21") (pin "2") (pinfunction "2_2") (pintype "input"))
      (node (ref "R9") (pin "2") (pinfunction "2_2") (pintype "input"))
      (node (ref "U1") (pin "1") (pinfunction "1_1") (pintype "unspecified"))
      (node (ref "U1") (pin "17") (pinfunction "17_17") (pintype "unspecified"))
      (node (ref "U10") (pin "2") (pinfunction "2_2") (pintype "unspecified"))
      (node (ref "U11") (pin "8") (pinfunction "VCC_8") (pintype "unspecified"))
      (node (ref "U13") (pin "4") (pinfunction "VDD_4") (pintype "unspecified"))
      (node (ref "U13") (pin "5") (pinfunction "/SHDN_5") (pintype "unspecified"))
      (node (ref "U14") (pin "16") (pinfunction "DVDD_16") (pintype "unspecified"))
      (node (ref "U2") (pin "1") (pinfunction "1_1") (pintype "unspecified"))
      (node (ref "U3") (pin "3") (pinfunction "VDD_3") (pintype "unspecified"))
      (node (ref "U31") (pin "2") (pinfunction "2_2") (pintype "unspecified"))
      (node (ref "U33") (pin "10") (pinfunction "MR#_10") (pintype "unspecified"))
      (node (ref "U33") (pin "16") (pinfunction "VCC_16") (pintype "unspecified"))
    )
    (net (code "62") (name "5V_Rasp") (class "Default")
      (node (ref "C20") (pin "1") (pinfunction "1_1") (pintype "input"))
      (node (ref "C25") (pin "1") (pinfunction "1_1") (pintype "unspecified"))
      (node (ref "C26") (pin "1") (pinfunction "1_1") (pintype "unspecified"))
      (node (ref "C27") (pin "1") (pinfunction "1_1") (pintype "unspecified"))
      (node (ref "R19") (pin "2") (pinfunction "2_2") (pintype "unspecified"))
      (node (ref "U1") (pin "2") (pinfunction "2_2") (pintype "unspecified"))
      (node (ref "U1") (pin "4") (pinfunction "4_4") (pintype "unspecified"))
      (node (ref "U21") (pin "3") (pinfunction "VOUT_3") (pintype "unspecified"))
    )
    (net (code "63") (name "7V") (class "Default")
      (node (ref "C21") (pin "2") (pinfunction "2_2") (pintype "unspecified"))
      (node (ref "CN1") (pin "5") (pinfunction "5_5") (pintype "unspecified"))
      (node (ref "CN1") (pin "7") (pinfunction "7_7") (pintype "unspecified"))
      (node (ref "D1") (pin "1") (pinfunction "K_1") (pintype "unspecified"))
      (node (ref "R31") (pin "2") (pinfunction "2_2") (pintype "unspecified"))
    )
    (net (code "64") (name "13V") (class "Default")
      (node (ref "C46") (pin "1") (pinfunction "1_1") (pintype "unspecified"))
      (node (ref "C47") (pin "1") (pinfunction "1_1") (pintype "unspecified"))
      (node (ref "C48") (pin "1") (pinfunction "1_1") (pintype "unspecified"))
      (node (ref "C49") (pin "1") (pinfunction "1_1") (pintype "unspecified"))
      (node (ref "C50") (pin "1") (pinfunction "1_1") (pintype "unspecified"))
      (node (ref "C51") (pin "1") (pinfunction "1_1") (pintype "unspecified"))
      (node (ref "CN2") (pin "1") (pinfunction "1_1") (pintype "unspecified"))
      (node (ref "U28") (pin "5") (pinfunction "VOUT_5") (pintype "unspecified"))
      (node (ref "U32") (pin "1") (pinfunction "1_1") (pintype "unspecified"))
    )
    (net (code "65") (name "GND") (class "Default")
      (node (ref "BATTERY_INPUT") (pin "2") (pinfunction "2_2") (pintype "unspecified"))
      (node (ref "C1") (pin "1") (pinfunction "1_1") (pintype "unspecified"))
      (node (ref "C10") (pin "2") (pinfunction "2_2") (pintype "unspecified"))
      (node (ref "C11") (pin "1") (pinfunction "1_1") (pintype "unspecified"))
      (node (ref "C12") (pin "1") (pinfunction "1_1") (pintype "unspecified"))
      (node (ref "C14") (pin "1") (pinfunction "1_1") (pintype "unspecified"))
      (node (ref "C15") (pin "1") (pinfunction "1_1") (pintype "unspecified"))
      (node (ref "C17") (pin "1") (pinfunction "1_1") (pintype "unspecified"))
      (node (ref "C18") (pin "1") (pinfunction "1_1") (pintype "unspecified"))
      (node (ref "C19") (pin "1") (pinfunction "1_1") (pintype "unspecified"))
      (node (ref "C2") (pin "1") (pinfunction "1_1") (pintype "unspecified"))
      (node (ref "C20") (pin "2") (pinfunction "2_2") (pintype "input"))
      (node (ref "C21") (pin "1") (pinfunction "1_1") (pintype "unspecified"))
      (node (ref "C22") (pin "1") (pinfunction "1_1") (pintype "unspecified"))
      (node (ref "C24") (pin "1") (pinfunction "1_1") (pintype "input"))
      (node (ref "C25") (pin "2") (pinfunction "2_2") (pintype "unspecified"))
      (node (ref "C26") (pin "2") (pinfunction "2_2") (pintype "unspecified"))
      (node (ref "C27") (pin "2") (pinfunction "2_2") (pintype "unspecified"))
      (node (ref "C28") (pin "1") (pinfunction "1_1") (pintype "unspecified"))
      (node (ref "C29") (pin "2") (pinfunction "2_2") (pintype "input"))
      (node (ref "C31") (pin "1") (pinfunction "1_1") (pintype "unspecified"))
      (node (ref "C33") (pin "2") (pinfunction "2_2") (pintype "unspecified"))
      (node (ref "C34") (pin "2") (pinfunction "2_2") (pintype "unspecified"))
      (node (ref "C35") (pin "2") (pinfunction "2_2") (pintype "unspecified"))
      (node (ref "C36") (pin "2") (pinfunction "2_2") (pintype "unspecified"))
      (node (ref "C37") (pin "2") (pinfunction "2_2") (pintype "unspecified"))
      (node (ref "C38") (pin "2") (pinfunction "2_2") (pintype "unspecified"))
      (node (ref "C39") (pin "2") (pinfunction "2_2") (pintype "unspecified"))
      (node (ref "C4") (pin "2") (pinfunction "2_2") (pintype "input"))
      (node (ref "C40") (pin "2") (pinfunction "2_2") (pintype "unspecified"))
      (node (ref "C41") (pin "1") (pinfunction "1_1") (pintype "unspecified"))
      (node (ref "C44") (pin "1") (pinfunction "1_1") (pintype "unspecified"))
      (node (ref "C45") (pin "1") (pinfunction "1_1") (pintype "input"))
      (node (ref "C46") (pin "2") (pinfunction "2_2") (pintype "unspecified"))
      (node (ref "C47") (pin "2") (pinfunction "2_2") (pintype "unspecified"))
      (node (ref "C48") (pin "2") (pinfunction "2_2") (pintype "unspecified"))
      (node (ref "C49") (pin "2") (pinfunction "2_2") (pintype "unspecified"))
      (node (ref "C5") (pin "2") (pinfunction "2_2") (pintype "unspecified"))
      (node (ref "C50") (pin "2") (pinfunction "2_2") (pintype "unspecified"))
      (node (ref "C51") (pin "2") (pinfunction "2_2") (pintype "unspecified"))
      (node (ref "C53") (pin "1") (pinfunction "1_1") (pintype "unspecified"))
      (node (ref "C55") (pin "2") (pinfunction "2_2") (pintype "unspecified"))
      (node (ref "C59") (pin "2") (pinfunction "2_2") (pintype "input"))
      (node (ref "C6") (pin "2") (pinfunction "2_2") (pintype "unspecified"))
      (node (ref "C60") (pin "2") (pinfunction "2_2") (pintype "unspecified"))
      (node (ref "C61") (pin "2") (pinfunction "2_2") (pintype "unspecified"))
      (node (ref "C62") (pin "2") (pinfunction "2_2") (pintype "unspecified"))
      (node (ref "C7") (pin "1") (pinfunction "1_1") (pintype "unspecified"))
      (node (ref "C8") (pin "1") (pinfunction "1_1") (pintype "unspecified"))
      (node (ref "C9") (pin "1") (pinfunction "1_1") (pintype "unspecified"))
      (node (ref "CHARGING") (pin "A12") (pinfunction "GND_A12") (pintype "unspecified"))
      (node (ref "CHARGING") (pin "B12") (pinfunction "GND_B12") (pintype "unspecified"))
      (node (ref "CN2") (pin "7") (pinfunction "7_7") (pintype "unspecified"))
      (node (ref "CN2") (pin "8") (pinfunction "8_8") (pintype "unspecified"))
      (node (ref "CN3") (pin "3") (pinfunction "3_3") (pintype "unspecified"))
      (node (ref "D2") (pin "3") (pinfunction "3_3") (pintype "unspecified"))
      (node (ref "J1") (pin "2") (pinfunction "2_2") (pintype "unspecified"))
      (node (ref "LED1") (pin "1") (pinfunction "K_1") (pintype "unspecified"))
      (node (ref "LOADCELL") (pin "2") (pinfunction "2_2") (pintype "unspecified"))
      (node (ref "LOADCELL") (pin "5") (pinfunction "5_5") (pintype "unspecified"))
      (node (ref "NIR") (pin "3") (pinfunction "3_3") (pintype "unspecified"))
      (node (ref "PUSHBUTTON") (pin "2") (pinfunction "2_2") (pintype "unspecified"))
      (node (ref "Q3") (pin "3") (pinfunction "E_3") (pintype "unspecified"))
      (node (ref "Q4") (pin "3") (pinfunction "S_3") (pintype "unspecified"))
      (node (ref "Q5") (pin "3") (pinfunction "S_3") (pintype "unspecified"))
      (node (ref "Q6") (pin "3") (pinfunction "S_3") (pintype "unspecified"))
      (node (ref "Q7") (pin "3") (pinfunction "S_3") (pintype "unspecified"))
      (node (ref "Q8") (pin "3") (pinfunction "E_3") (pintype "input"))
      (node (ref "R15") (pin "1") (pinfunction "1_1") (pintype "input"))
      (node (ref "R16") (pin "1") (pinfunction "1_1") (pintype "input"))
      (node (ref "R17") (pin "2") (pinfunction "2_2") (pintype "unspecified"))
      (node (ref "R2") (pin "1") (pinfunction "1_1") (pintype "unspecified"))
      (node (ref "R20") (pin "1") (pinfunction "1_1") (pintype "unspecified"))
      (node (ref "R25") (pin "1") (pinfunction "1_1") (pintype "input"))
      (node (ref "R26") (pin "1") (pinfunction "1_1") (pintype "unspecified"))
      (node (ref "R29") (pin "1") (pinfunction "1_1") (pintype "input"))
      (node (ref "R32") (pin "1") (pinfunction "1_1") (pintype "input"))
      (node (ref "R33") (pin "1") (pinfunction "1_1") (pintype "unspecified"))
      (node (ref "R35") (pin "1") (pinfunction "1_1") (pintype "unspecified"))
      (node (ref "R37") (pin "1") (pinfunction "1_1") (pintype "input"))
      (node (ref "R4") (pin "2") (pinfunction "2_2") (pintype "unspecified"))
      (node (ref "R6") (pin "1") (pinfunction "1_1") (pintype "input"))
      (node (ref "REEDSWITCH") (pin "2") (pinfunction "2_2") (pintype "unspecified"))
      (node (ref "REEDSWITCH1") (pin "2") (pinfunction "2_2") (pintype "unspecified"))
      (node (ref "U1") (pin "14") (pinfunction "14_14") (pintype "unspecified"))
      (node (ref "U1") (pin "20") (pinfunction "20_20") (pintype "unspecified"))
      (node (ref "U1") (pin "25") (pinfunction "25_25") (pintype "unspecified"))
      (node (ref "U1") (pin "30") (pinfunction "30_30") (pintype "unspecified"))
      (node (ref "U1") (pin "34") (pinfunction "34_34") (pintype "unspecified"))
      (node (ref "U1") (pin "39") (pinfunction "39_39") (pintype "unspecified"))
      (node (ref "U1") (pin "6") (pinfunction "6_6") (pintype "unspecified"))
      (node (ref "U1") (pin "9") (pinfunction "9_9") (pintype "unspecified"))
      (node (ref "U10") (pin "1") (pinfunction "1_1") (pintype "unspecified"))
      (node (ref "U11") (pin "10") (pinfunction "GND_10") (pintype "unspecified"))
      (node (ref "U11") (pin "12") (pinfunction "GND_12") (pintype "unspecified"))
      (node (ref "U12") (pin "3") (pinfunction "GND_3") (pintype "unspecified"))
      (node (ref "U13") (pin "1") (pinfunction "GND_1") (pintype "unspecified"))
      (node (ref "U13") (pin "2") (pinfunction "GND_2") (pintype "unspecified"))
      (node (ref "U14") (pin "14") (pinfunction "XI_14") (pintype "unspecified"))
      (node (ref "U14") (pin "5") (pinfunction "AGND_5") (pintype "unspecified"))
      (node (ref "U16") (pin "3") (pinfunction "GND_3") (pintype "unspecified"))
      (node (ref "U16") (pin "7") (pinfunction "A0_7") (pintype "unspecified"))
      (node (ref "U16") (pin "8") (pinfunction "A1_8") (pintype "unspecified"))
      (node (ref "U17") (pin "1") (pinfunction "1_1") (pintype "unspecified"))
      (node (ref "U18") (pin "14") (pinfunction "VSS_14") (pintype "unspecified"))
      (node (ref "U18") (pin "25") (pinfunction "EXTCLK_25") (pintype "unspecified"))
      (node (ref "U19") (pin "1") (pinfunction "GND_1") (pintype "unspecified"))
      (node (ref "U2") (pin "2") (pinfunction "2_2") (pintype "unspecified"))
      (node (ref "U20") (pin "2") (pinfunction "GND_2") (pintype "unspecified"))
      (node (ref "U21") (pin "1") (pinfunction "GND_1") (pintype "unspecified"))
      (node (ref "U23") (pin "1") (pinfunction "1_1") (pintype "unspecified"))
      (node (ref "U24") (pin "1") (pinfunction "1_1") (pintype "unspecified"))
      (node (ref "U25") (pin "10") (pinfunction "ACDRV2_10") (pintype "unspecified"))
      (node (ref "U25") (pin "11") (pinfunction "ACDRV1_11") (pintype "unspecified"))
      (node (ref "U25") (pin "27") (pinfunction "GND_27") (pintype "unspecified"))
      (node (ref "U26") (pin "1") (pinfunction "1_1") (pintype "unspecified"))
      (node (ref "U28") (pin "10") (pinfunction "AGND_10") (pintype "unspecified"))
      (node (ref "U28") (pin "3") (pinfunction "PGND_3") (pintype "unspecified"))
      (node (ref "U30") (pin "11") (pinfunction "GND_11") (pintype "unspecified"))
      (node (ref "U30") (pin "15") (pinfunction "PGNDR_15") (pintype "unspecified"))
      (node (ref "U30") (pin "2") (pinfunction "PGNDL_2") (pintype "unspecified"))
      (node (ref "U31") (pin "1") (pinfunction "1_1") (pintype "unspecified"))
      (node (ref "U33") (pin "13") (pinfunction "OE#_13") (pintype "unspecified"))
      (node (ref "U33") (pin "8") (pinfunction "GND_8") (pintype "unspecified"))
      (node (ref "U34") (pin "1") (pinfunction "1_1") (pintype "unspecified"))
      (node (ref "U35") (pin "1") (pinfunction "1_1") (pintype "unspecified"))
      (node (ref "U36") (pin "1") (pinfunction "1_1") (pintype "unspecified"))
      (node (ref "U4") (pin "3") (pinfunction "GND_3") (pintype "unspecified"))
      (node (ref "U5") (pin "10") (pinfunction "SYNC_10") (pintype "unspecified"))
      (node (ref "U5") (pin "13") (pinfunction "GND_13") (pintype "unspecified"))
      (node (ref "U5") (pin "17") (pinfunction "EPAD_17") (pintype "unspecified"))
      (node (ref "U5") (pin "5") (pinfunction "PGND_5") (pintype "unspecified"))
      (node (ref "U5") (pin "6") (pinfunction "PGND_6") (pintype "unspecified"))
      (node (ref "U5") (pin "7") (pinfunction "PGND_7") (pintype "unspecified"))
      (node (ref "U8") (pin "1") (pinfunction "1_1") (pintype "input"))
    )
    (net (code "66") (name "Net-(ANT1-Pad1)") (class "Default")
      (node (ref "ANT1") (pin "1") (pinfunction "1_1") (pintype "unspecified"))
      (node (ref "C23") (pin "2") (pinfunction "2_2") (pintype "unspecified"))
    )
    (net (code "67") (name "Net-(C3-Pad2)") (class "Default")
      (node (ref "C3") (pin "2") (pinfunction "2_2") (pintype "unspecified"))
      (node (ref "C42") (pin "2") (pinfunction "2_2") (pintype "unspecified"))
      (node (ref "U22") (pin "1") (pinfunction "1_1") (pintype "unspecified"))
      (node (ref "U9") (pin "1") (pinfunction "1_1") (pintype "unspecified"))
    )
    (net (code "68") (name "Net-(C23-Pad1)") (class "Default")
      (node (ref "C23") (pin "1") (pinfunction "1_1") (pintype "unspecified"))
      (node (ref "L2") (pin "2") (pinfunction "2_2") (pintype "unspecified"))
    )
    (net (code "69") (name "Net-(C52-Pad1)") (class "Default")
      (node (ref "C52") (pin "1") (pinfunction "1_1") (pintype "input"))
      (node (ref "R32") (pin "2") (pinfunction "2_2") (pintype "input"))
    )
    (net (code "70") (name "Net-(C57-Pad2)") (class "Default")
      (node (ref "C57") (pin "2") (pinfunction "2_2") (pintype "unspecified"))
      (node (ref "CN3") (pin "4") (pinfunction "4_4") (pintype "unspecified"))
    )
    (net (code "71") (name "Net-(C58-Pad2)") (class "Default")
      (node (ref "C58") (pin "2") (pinfunction "2_2") (pintype "unspecified"))
      (node (ref "CN3") (pin "1") (pinfunction "1_1") (pintype "unspecified"))
    )
    (net (code "72") (name "Net-(CHARGING-CC1)") (class "Default")
      (node (ref "CHARGING") (pin "A5") (pinfunction "CC1_A5") (pintype "unspecified"))
      (node (ref "R16") (pin "2") (pinfunction "2_2") (pintype "input"))
    )
    (net (code "73") (name "Net-(CHARGING-CC2)") (class "Default")
      (node (ref "CHARGING") (pin "B5") (pinfunction "CC2_B5") (pintype "unspecified"))
      (node (ref "R25") (pin "2") (pinfunction "2_2") (pintype "input"))
    )
    (net (code "74") (name "Net-(D1-A)") (class "Default")
      (node (ref "D1") (pin "2") (pinfunction "A_2") (pintype "unspecified"))
      (node (ref "L1") (pin "2") (pinfunction "2_2") (pintype "unspecified"))
      (node (ref "U20") (pin "1") (pinfunction "SW_1") (pintype "unspecified"))
    )
    (net (code "75") (name "Net-(LED1-A)") (class "Default")
      (node (ref "LED1") (pin "2") (pinfunction "A_2") (pintype "unspecified"))
      (node (ref "R34") (pin "1") (pinfunction "1_1") (pintype "unspecified"))
    )
    (net (code "76") (name "Net-(NIR-Pad1)") (class "Default")
      (node (ref "NIR") (pin "1") (pinfunction "1_1") (pintype "unspecified"))
      (node (ref "R13") (pin "2") (pinfunction "2_2") (pintype "unspecified"))
    )
    (net (code "77") (name "Net-(Q1-C)") (class "Default")
      (node (ref "Q1") (pin "3") (pinfunction "C_3") (pintype "unspecified"))
      (node (ref "R34") (pin "2") (pinfunction "2_2") (pintype "unspecified"))
    )
    (net (code "78") (name "Net-(Q3-B)") (class "Default")
      (node (ref "Q3") (pin "1") (pinfunction "B_1") (pintype "unspecified"))
      (node (ref "R12") (pin "1") (pinfunction "1_1") (pintype "unspecified"))
    )
    (net (code "79") (name "Net-(Q3-C)") (class "Default")
      (node (ref "BUZZER") (pin "2") (pinfunction "2_2") (pintype "unspecified"))
      (node (ref "Q3") (pin "2") (pinfunction "C_2") (pintype "unspecified"))
    )
    (net (code "80") (name "Net-(Q4-G)") (class "Default")
      (node (ref "Q4") (pin "1") (pinfunction "G_1") (pintype "unspecified"))
      (node (ref "U4") (pin "7") (pinfunction "OUTA_7") (pintype "unspecified"))
    )
    (net (code "81") (name "Net-(Q5-G)") (class "Default")
      (node (ref "Q5") (pin "1") (pinfunction "G_1") (pintype "unspecified"))
      (node (ref "U4") (pin "5") (pinfunction "OUTB_5") (pintype "unspecified"))
    )
    (net (code "82") (name "Net-(Q6-G)") (class "Default")
      (node (ref "Q6") (pin "1") (pinfunction "G_1") (pintype "unspecified"))
      (node (ref "U12") (pin "7") (pinfunction "OUTA_7") (pintype "unspecified"))
    )
    (net (code "83") (name "Net-(Q7-G)") (class "Default")
      (node (ref "Q7") (pin "1") (pinfunction "G_1") (pintype "unspecified"))
      (node (ref "U12") (pin "5") (pinfunction "OUTB_5") (pintype "unspecified"))
    )
    (net (code "84") (name "Net-(Q8-B)") (class "Default")
      (node (ref "Q8") (pin "1") (pinfunction "B_1") (pintype "input"))
      (node (ref "R14") (pin "2") (pinfunction "2_2") (pintype "unspecified"))
    )
    (net (code "85") (name "Net-(Q8-C)") (class "Default")
      (node (ref "FAN") (pin "1") (pinfunction "1_1") (pintype "unspecified"))
      (node (ref "Q8") (pin "2") (pinfunction "C_2") (pintype "input"))
    )
    (net (code "86") (name "Net-(Q10-B)") (class "Default")
      (node (ref "Q10") (pin "1") (pinfunction "B_1") (pintype "input"))
      (node (ref "U14") (pin "2") (pinfunction "BASE_2") (pintype "unspecified"))
    )
    (net (code "87") (name "Net-(Q10-C)") (class "Default")
      (node (ref "Q10") (pin "3") (pinfunction "C_3") (pintype "input"))
      (node (ref "R27") (pin "2") (pinfunction "2_2") (pintype "unspecified"))
      (node (ref "U14") (pin "3") (pinfunction "AVDD_3") (pintype "unspecified"))
      (node (ref "U15") (pin "2") (pinfunction "2_2") (pintype "unspecified"))
    )
    (net (code "88") (name "Net-(R15-Pad3)") (class "Default")
      (node (ref "R15") (pin "3") (pinfunction "3_3") (pintype "input"))
      (node (ref "R31") (pin "1") (pinfunction "1_1") (pintype "unspecified"))
    )
    (net (code "89") (name "Net-(U3-VSS)") (class "Default")
      (node (ref "C19") (pin "2") (pinfunction "2_2") (pintype "unspecified"))
      (node (ref "U3") (pin "4") (pinfunction "VSS_4") (pintype "unspecified"))
    )
    (net (code "90") (name "Net-(U5-FB)") (class "Default")
      (node (ref "R3") (pin "1") (pinfunction "1_1") (pintype "input"))
      (node (ref "U5") (pin "14") (pinfunction "FB_14") (pintype "unspecified"))
      (node (ref "U8") (pin "2") (pinfunction "2_2") (pintype "input"))
    )
    (net (code "91") (name "Net-(U5-SW-Pad3)") (class "Default")
      (node (ref "U5") (pin "3") (pinfunction "SW_3") (pintype "unspecified"))
      (node (ref "U5") (pin "4") (pinfunction "SW_4") (pintype "unspecified"))
      (node (ref "U7") (pin "1") (pinfunction "1_1") (pintype "unspecified"))
    )
    (net (code "92") (name "Net-(U11-RF_IN)") (class "Default")
      (node (ref "U11") (pin "11") (pinfunction "RF_IN_11") (pintype "unspecified"))
      (node (ref "U13") (pin "6") (pinfunction "RFOUT_6") (pintype "unspecified"))
    )
    (net (code "93") (name "Net-(U13-RFIN)") (class "Default")
      (node (ref "L2") (pin "1") (pinfunction "1_1") (pintype "unspecified"))
      (node (ref "U13") (pin "3") (pinfunction "RFIN_3") (pintype "unspecified"))
    )
    (net (code "94") (name "Net-(U14-INNA)") (class "Default")
      (node (ref "C13") (pin "2") (pinfunction "2_2") (pintype "unspecified"))
      (node (ref "R7") (pin "2") (pinfunction "2_2") (pintype "unspecified"))
      (node (ref "U14") (pin "7") (pinfunction "INNA_7") (pintype "unspecified"))
    )
    (net (code "95") (name "Net-(U14-INPA)") (class "Default")
      (node (ref "C13") (pin "1") (pinfunction "1_1") (pintype "unspecified"))
      (node (ref "R28") (pin "2") (pinfunction "2_2") (pintype "unspecified"))
      (node (ref "U14") (pin "8") (pinfunction "INPA_8") (pintype "unspecified"))
    )
    (net (code "96") (name "Net-(U14-RATE)") (class "Default")
      (node (ref "J1") (pin "1") (pinfunction "1_1") (pintype "unspecified"))
      (node (ref "R8") (pin "1") (pinfunction "1_1") (pintype "input"))
      (node (ref "U14") (pin "15") (pinfunction "RATE_15") (pintype "unspecified"))
    )
    (net (code "97") (name "Net-(U14-VBG)") (class "Default")
      (node (ref "C6") (pin "1") (pinfunction "1_1") (pintype "unspecified"))
      (node (ref "U14") (pin "6") (pinfunction "VBG_6") (pintype "unspecified"))
    )
    (net (code "98") (name "Net-(U14-VFB)") (class "Default")
      (node (ref "R27") (pin "1") (pinfunction "1_1") (pintype "unspecified"))
      (node (ref "R6") (pin "2") (pinfunction "2_2") (pintype "input"))
      (node (ref "U14") (pin "4") (pinfunction "VFB_4") (pintype "unspecified"))
    )
    (net (code "99") (name "Net-(U16-IN+)") (class "Default")
      (node (ref "C56") (pin "1") (pinfunction "1_1") (pintype "unspecified"))
      (node (ref "R30") (pin "2") (pinfunction "2_2") (pintype "input"))
      (node (ref "U16") (pin "1") (pinfunction "IN+_1") (pintype "unspecified"))
    )
    (net (code "100") (name "Net-(U16-IN–)") (class "Default")
      (node (ref "C56") (pin "2") (pinfunction "2_2") (pintype "unspecified"))
      (node (ref "R29") (pin "2") (pinfunction "2_2") (pintype "input"))
      (node (ref "U16") (pin "2") (pinfunction "IN–_2") (pintype "unspecified"))
    )
    (net (code "101") (name "Net-(U18-LED0)") (class "Default")
      (node (ref "U18") (pin "6") (pinfunction "LED0_6") (pintype "unspecified"))
      (node (ref "U23") (pin "3") (pinfunction "3_3") (pintype "unspecified"))
    )
    (net (code "102") (name "Net-(U18-LED1)") (class "Default")
      (node (ref "U18") (pin "7") (pinfunction "LED1_7") (pintype "unspecified"))
      (node (ref "U34") (pin "3") (pinfunction "3_3") (pintype "unspecified"))
    )
    (net (code "103") (name "Net-(U18-LED2)") (class "Default")
      (node (ref "U18") (pin "8") (pinfunction "LED2_8") (pintype "unspecified"))
      (node (ref "U35") (pin "3") (pinfunction "3_3") (pintype "unspecified"))
    )
    (net (code "104") (name "Net-(U18-LED3)") (class "Default")
      (node (ref "U18") (pin "9") (pinfunction "LED3_9") (pintype "unspecified"))
      (node (ref "U36") (pin "3") (pinfunction "3_3") (pintype "unspecified"))
    )
    (net (code "105") (name "Net-(U18-OE#)") (class "Default")
      (node (ref "R37") (pin "2") (pinfunction "2_2") (pintype "input"))
      (node (ref "U18") (pin "23") (pinfunction "OE#_23") (pintype "unspecified"))
    )
    (net (code "106") (name "Net-(U20-FB)") (class "Default")
      (node (ref "R15") (pin "2") (pinfunction "2_2") (pintype "input"))
      (node (ref "U20") (pin "3") (pinfunction "FB_3") (pintype "unspecified"))
    )
    (net (code "107") (name "Net-(U21-FB)") (class "Default")
      (node (ref "R19") (pin "1") (pinfunction "1_1") (pintype "unspecified"))
      (node (ref "R33") (pin "2") (pinfunction "2_2") (pintype "unspecified"))
      (node (ref "U21") (pin "4") (pinfunction "FB_4") (pintype "unspecified"))
    )
    (net (code "108") (name "Net-(U21-SW)") (class "Default")
      (node (ref "L3") (pin "2") (pinfunction "2_2") (pintype "unspecified"))
      (node (ref "U21") (pin "2") (pinfunction "SW_2") (pintype "unspecified"))
    )
    (net (code "109") (name "Net-(U21-VIN)") (class "Default")
      (node (ref "C24") (pin "2") (pinfunction "2_2") (pintype "input"))
      (node (ref "F1") (pin "2") (pinfunction "2_2") (pintype "unspecified"))
      (node (ref "L3") (pin "1") (pinfunction "1_1") (pintype "unspecified"))
      (node (ref "U21") (pin "7") (pinfunction "VIN_7") (pintype "unspecified"))
    )
    (net (code "110") (name "Net-(U25-PMID)") (class "Default")
      (node (ref "C33") (pin "1") (pinfunction "1_1") (pintype "unspecified"))
      (node (ref "C34") (pin "1") (pinfunction "1_1") (pintype "unspecified"))
      (node (ref "C35") (pin "1") (pinfunction "1_1") (pintype "unspecified"))
      (node (ref "U24") (pin "2") (pinfunction "2_2") (pintype "unspecified"))
      (node (ref "U25") (pin "29") (pinfunction "PMID_29") (pintype "unspecified"))
    )
    (net (code "111") (name "Net-(U25-PROG)") (class "Default")
      (node (ref "R4") (pin "1") (pinfunction "1_1") (pintype "unspecified"))
      (node (ref "U25") (pin "20") (pinfunction "PROG_20") (pintype "unspecified"))
    )
    (net (code "112") (name "Net-(U25-STAT)") (class "Default")
      (node (ref "U25") (pin "1") (pinfunction "STAT_1") (pintype "unspecified"))
      (node (ref "U27") (pin "1") (pinfunction "K_1") (pintype "unspecified"))
    )
    (net (code "113") (name "Net-(U25-TS)") (class "Default")
      (node (ref "D2") (pin "1") (pinfunction "1_1") (pintype "unspecified"))
      (node (ref "D2") (pin "2") (pinfunction "2_2") (pintype "unspecified"))
      (node (ref "R26") (pin "2") (pinfunction "2_2") (pintype "unspecified"))
      (node (ref "U25") (pin "16") (pinfunction "TS_16") (pintype "unspecified"))
      (node (ref "U29") (pin "1") (pinfunction "1_1") (pintype "unspecified"))
    )
    (net (code "114") (name "Net-(U25-VAC1)") (class "Default")
      (node (ref "U25") (pin "8") (pinfunction "VAC2_8") (pintype "unspecified"))
      (node (ref "U25") (pin "9") (pinfunction "VAC1_9") (pintype "unspecified"))
    )
    (net (code "115") (name "Net-(U27-A)") (class "Default")
      (node (ref "R5") (pin "2") (pinfunction "2_2") (pintype "unspecified"))
      (node (ref "U27") (pin "2") (pinfunction "A_2") (pintype "unspecified"))
    )
    (net (code "116") (name "Net-(U28-VCC)") (class "Default")
      (node (ref "C44") (pin "2") (pinfunction "2_2") (pintype "unspecified"))
      (node (ref "U28") (pin "11") (pinfunction "VCC_11") (pintype "unspecified"))
    )
    (net (code "117") (name "Net-(U30-+OUT_L)") (class "Default")
      (node (ref "CN6") (pin "1") (pinfunction "1_1") (pintype "unspecified"))
      (node (ref "U30") (pin "1") (pinfunction "+OUT_L_1") (pintype "unspecified"))
    )
    (net (code "118") (name "Net-(U30-+OUT_R)") (class "Default")
      (node (ref "CN5") (pin "1") (pinfunction "1_1") (pintype "unspecified"))
      (node (ref "U30") (pin "16") (pinfunction "+OUT_R_16") (pintype "unspecified"))
    )
    (net (code "119") (name "Net-(U30--OUT_L)") (class "Default")
      (node (ref "CN6") (pin "2") (pinfunction "2_2") (pintype "unspecified"))
      (node (ref "U30") (pin "3") (pinfunction "-OUT_L_3") (pintype "unspecified"))
    )
    (net (code "120") (name "Net-(U30--OUT_R)") (class "Default")
      (node (ref "CN5") (pin "2") (pinfunction "2_2") (pintype "unspecified"))
      (node (ref "U30") (pin "14") (pinfunction "-OUT_R_14") (pintype "unspecified"))
    )
    (net (code "121") (name "Net-(U30-INL)") (class "Default")
      (node (ref "C58") (pin "1") (pinfunction "1_1") (pintype "unspecified"))
      (node (ref "U30") (pin "7") (pinfunction "INL_7") (pintype "unspecified"))
    )
    (net (code "122") (name "Net-(U30-INR)") (class "Default")
      (node (ref "C57") (pin "1") (pinfunction "1_1") (pintype "unspecified"))
      (node (ref "U30") (pin "10") (pinfunction "INR_10") (pintype "unspecified"))
    )
    (net (code "123") (name "REGN") (class "Default")
      (node (ref "R36") (pin "1") (pinfunction "1_1") (pintype "unspecified"))
      (node (ref "R5") (pin "1") (pinfunction "1_1") (pintype "unspecified"))
      (node (ref "U29") (pin "2") (pinfunction "2_2") (pintype "unspecified"))
    )
    (net (code "124") (name "VLED") (class "Default")
      (node (ref "C14") (pin "2") (pinfunction "2_2") (pintype "unspecified"))
      (node (ref "U19") (pin "2") (pinfunction "VOUT_2") (pintype "unspecified"))
      (node (ref "U19") (pin "4") (pinfunction "VOUT_4") (pintype "unspecified"))
    )
    (net (code "125") (name "VUSB") (class "Default")
      (node (ref "C1") (pin "2") (pinfunction "2_2") (pintype "unspecified"))
      (node (ref "C3") (pin "1") (pinfunction "1_1") (pintype "unspecified"))
      (node (ref "C42") (pin "1") (pinfunction "1_1") (pintype "unspecified"))
      (node (ref "CHARGING") (pin "A9") (pinfunction "VBUS_A9") (pintype "unspecified"))
      (node (ref "CHARGING") (pin "B9") (pinfunction "VBUS_B9") (pintype "unspecified"))
      (node (ref "U22") (pin "2") (pinfunction "2_2") (pintype "unspecified"))
      (node (ref "U25") (pin "2") (pinfunction "VBUS_2") (pintype "unspecified"))
      (node (ref "U25") (pin "3") (pinfunction "VBUS_3") (pintype "unspecified"))
      (node (ref "U9") (pin "2") (pinfunction "2_2") (pintype "unspecified"))
    )
    (net (code "126") (name "V_BAT") (class "Default")
      (node (ref "C2") (pin "2") (pinfunction "2_2") (pintype "unspecified"))
      (node (ref "C22") (pin "2") (pinfunction "2_2") (pintype "unspecified"))
      (node (ref "C36") (pin "1") (pinfunction "1_1") (pintype "unspecified"))
      (node (ref "C37") (pin "1") (pinfunction "1_1") (pintype "unspecified"))
      (node (ref "C38") (pin "1") (pinfunction "1_1") (pintype "unspecified"))
      (node (ref "C4") (pin "1") (pinfunction "1_1") (pintype "input"))
      (node (ref "C5") (pin "1") (pinfunction "1_1") (pintype "unspecified"))
      (node (ref "C53") (pin "2") (pinfunction "2_2") (pintype "unspecified"))
      (node (ref "C55") (pin "1") (pinfunction "1_1") (pintype "unspecified"))
      (node (ref "C7") (pin "2") (pinfunction "2_2") (pintype "unspecified"))
      (node (ref "F1") (pin "1") (pinfunction "1_1") (pintype "unspecified"))
      (node (ref "FAN") (pin "2") (pinfunction "2_2") (pintype "unspecified"))
      (node (ref "L1") (pin "1") (pinfunction "1_1") (pintype "unspecified"))
      (node (ref "L5") (pin "2") (pinfunction "2_2") (pintype "unspecified"))
      (node (ref "Q1") (pin "2") (pinfunction "E_2") (pintype "unspecified"))
      (node (ref "R1") (pin "2") (pinfunction "2_2") (pintype "input"))
      (node (ref "R22") (pin "2") (pinfunction "2_2") (pintype "input"))
      (node (ref "R23") (pin "2") (pinfunction "2_2") (pintype "input"))
      (node (ref "U11") (pin "6") (pinfunction "VBAT_6") (pintype "unspecified"))
      (node (ref "U16") (pin "4") (pinfunction "VS_4") (pintype "unspecified"))
      (node (ref "U17") (pin "2") (pinfunction "2_2") (pintype "unspecified"))
      (node (ref "U19") (pin "3") (pinfunction "VIN_3") (pintype "unspecified"))
      (node (ref "U20") (pin "4") (pinfunction "EN_4") (pintype "unspecified"))
      (node (ref "U20") (pin "5") (pinfunction "IN_5") (pintype "unspecified"))
      (node (ref "U25") (pin "25") (pinfunction "SYS_25") (pintype "unspecified"))
      (node (ref "U26") (pin "2") (pinfunction "2_2") (pintype "unspecified"))
      (node (ref "U28") (pin "7") (pinfunction "VIN_7") (pintype "unspecified"))
      (node (ref "U5") (pin "8") (pinfunction "VBAT_8") (pintype "unspecified"))
      (node (ref "U6") (pin "2") (pinfunction "2_2") (pintype "input"))
      (node (ref "U7") (pin "2") (pinfunction "2_2") (pintype "unspecified"))
    )
    (net (code "127") (name "unconnected-(CHARGING-EH-Pad7)") (class "Default")
      (node (ref "CHARGING") (pin "7") (pinfunction "EH_7") (pintype "unspecified+no_connect"))
    )
    (net (code "128") (name "unconnected-(CN3-Pad2)") (class "Default")
      (node (ref "CN3") (pin "2") (pinfunction "2_2") (pintype "unspecified+no_connect"))
    )
    (net (code "129") (name "unconnected-(LOADCELL-Pad6)") (class "Default")
      (node (ref "LOADCELL") (pin "6") (pinfunction "6_6") (pintype "unspecified"))
    )
    (net (code "130") (name "unconnected-(LOADCELL-Pad7)") (class "Default")
      (node (ref "LOADCELL") (pin "7") (pinfunction "7_7") (pintype "unspecified"))
    )
    (net (code "131") (name "unconnected-(NIR-Pad4)") (class "Default")
      (node (ref "NIR") (pin "4") (pinfunction "4_4") (pintype "unspecified"))
    )
    (net (code "132") (name "unconnected-(NIR-Pad5)") (class "Default")
      (node (ref "NIR") (pin "5") (pinfunction "5_5") (pintype "unspecified"))
    )
    (net (code "133") (name "unconnected-(U3-EP-Pad5)") (class "Default")
      (node (ref "U3") (pin "5") (pinfunction "EP_5") (pintype "unspecified"))
    )
    (net (code "134") (name "unconnected-(U4-ENA-Pad1)") (class "Default")
      (node (ref "U4") (pin "1") (pinfunction "ENA_1") (pintype "unspecified"))
    )
    (net (code "135") (name "unconnected-(U4-ENB-Pad8)") (class "Default")
      (node (ref "U4") (pin "8") (pinfunction "ENB_8") (pintype "unspecified"))
    )
    (net (code "136") (name "unconnected-(U5-NC-Pad2)") (class "Default")
      (node (ref "U5") (pin "2") (pinfunction "NC_2") (pintype "unspecified"))
    )
    (net (code "137") (name "unconnected-(U11-GND-Pad1)") (class "Default")
      (node (ref "U11") (pin "1") (pinfunction "GND_1") (pintype "unspecified"))
    )
    (net (code "138") (name "unconnected-(U11-NC-Pad7)") (class "Default")
      (node (ref "U11") (pin "7") (pinfunction "NC_7") (pintype "unspecified"))
    )
    (net (code "139") (name "unconnected-(U11-NC-Pad13)") (class "Default")
      (node (ref "U11") (pin "13") (pinfunction "NC_13") (pintype "unspecified"))
    )
    (net (code "140") (name "unconnected-(U11-NRESET-Pad9)") (class "Default")
      (node (ref "U11") (pin "9") (pinfunction "NRESET_9") (pintype "unspecified"))
    )
    (net (code "141") (name "unconnected-(U11-Reserved-Pad15)") (class "Default")
      (node (ref "U11") (pin "15") (pinfunction "Reserved_15") (pintype "unspecified"))
    )
    (net (code "142") (name "unconnected-(U11-Reserved-Pad18)") (class "Default")
      (node (ref "U11") (pin "18") (pinfunction "Reserved_18") (pintype "unspecified"))
    )
    (net (code "143") (name "unconnected-(U11-SCL-Pad17)") (class "Default")
      (node (ref "U11") (pin "17") (pinfunction "SCL_17") (pintype "unspecified"))
    )
    (net (code "144") (name "unconnected-(U11-SDA-Pad16)") (class "Default")
      (node (ref "U11") (pin "16") (pinfunction "SDA_16") (pintype "unspecified"))
    )
    (net (code "145") (name "unconnected-(U11-VCC_RF-Pad14)") (class "Default")
      (node (ref "U11") (pin "14") (pinfunction "VCC_RF_14") (pintype "unspecified"))
    )
    (net (code "146") (name "unconnected-(U12-ENA-Pad1)") (class "Default")
      (node (ref "U12") (pin "1") (pinfunction "ENA_1") (pintype "unspecified"))
    )
    (net (code "147") (name "unconnected-(U12-ENB-Pad8)") (class "Default")
      (node (ref "U12") (pin "8") (pinfunction "ENB_8") (pintype "unspecified"))
    )
    (net (code "148") (name "unconnected-(U14-INNB-Pad9)") (class "Default")
      (node (ref "U14") (pin "9") (pinfunction "INNB_9") (pintype "unspecified"))
    )
    (net (code "149") (name "unconnected-(U14-INPB-Pad10)") (class "Default")
      (node (ref "U14") (pin "10") (pinfunction "INPB_10") (pintype "unspecified"))
    )
    (net (code "150") (name "unconnected-(U14-XO-Pad13)") (class "Default")
      (node (ref "U14") (pin "13") (pinfunction "XO_13") (pintype "unspecified"))
    )
    (net (code "151") (name "unconnected-(U18-A0-Pad1)") (class "Default")
      (node (ref "U18") (pin "1") (pinfunction "A0_1") (pintype "unspecified"))
    )
    (net (code "152") (name "unconnected-(U18-A1-Pad2)") (class "Default")
      (node (ref "U18") (pin "2") (pinfunction "A1_2") (pintype "unspecified"))
    )
    (net (code "153") (name "unconnected-(U18-A2-Pad3)") (class "Default")
      (node (ref "U18") (pin "3") (pinfunction "A2_3") (pintype "unspecified"))
    )
    (net (code "154") (name "unconnected-(U18-A3-Pad4)") (class "Default")
      (node (ref "U18") (pin "4") (pinfunction "A3_4") (pintype "unspecified"))
    )
    (net (code "155") (name "unconnected-(U18-A4-Pad5)") (class "Default")
      (node (ref "U18") (pin "5") (pinfunction "A4_5") (pintype "unspecified"))
    )
    (net (code "156") (name "unconnected-(U18-A5-Pad24)") (class "Default")
      (node (ref "U18") (pin "24") (pinfunction "A5_24") (pintype "unspecified"))
    )
    (net (code "157") (name "unconnected-(U18-LED4-Pad10)") (class "Default")
      (node (ref "U18") (pin "10") (pinfunction "LED4_10") (pintype "unspecified"))
    )
    (net (code "158") (name "unconnected-(U18-LED5-Pad11)") (class "Default")
      (node (ref "U18") (pin "11") (pinfunction "LED5_11") (pintype "unspecified"))
    )
    (net (code "159") (name "unconnected-(U18-LED6-Pad12)") (class "Default")
      (node (ref "U18") (pin "12") (pinfunction "LED6_12") (pintype "unspecified"))
    )
    (net (code "160") (name "unconnected-(U18-LED7-Pad13)") (class "Default")
      (node (ref "U18") (pin "13") (pinfunction "LED7_13") (pintype "unspecified"))
    )
    (net (code "161") (name "unconnected-(U18-LED8-Pad15)") (class "Default")
      (node (ref "U18") (pin "15") (pinfunction "LED8_15") (pintype "unspecified"))
    )
    (net (code "162") (name "unconnected-(U18-LED9-Pad16)") (class "Default")
      (node (ref "U18") (pin "16") (pinfunction "LED9_16") (pintype "unspecified"))
    )
    (net (code "163") (name "unconnected-(U18-LED10-Pad17)") (class "Default")
      (node (ref "U18") (pin "17") (pinfunction "LED10_17") (pintype "unspecified"))
    )
    (net (code "164") (name "unconnected-(U18-LED11-Pad18)") (class "Default")
      (node (ref "U18") (pin "18") (pinfunction "LED11_18") (pintype "unspecified"))
    )
    (net (code "165") (name "unconnected-(U18-LED12-Pad19)") (class "Default")
      (node (ref "U18") (pin "19") (pinfunction "LED12_19") (pintype "unspecified"))
    )
    (net (code "166") (name "unconnected-(U18-LED13-Pad20)") (class "Default")
      (node (ref "U18") (pin "20") (pinfunction "LED13_20") (pintype "unspecified"))
    )
    (net (code "167") (name "unconnected-(U18-LED14-Pad21)") (class "Default")
      (node (ref "U18") (pin "21") (pinfunction "LED14_21") (pintype "unspecified"))
    )
    (net (code "168") (name "unconnected-(U18-LED15-Pad22)") (class "Default")
      (node (ref "U18") (pin "22") (pinfunction "LED15_22") (pintype "unspecified"))
    )
    (net (code "169") (name "unconnected-(U20-NC-Pad6)") (class "Default")
      (node (ref "U20") (pin "6") (pinfunction "NC_6") (pintype "unspecified"))
    )
    (net (code "170") (name "unconnected-(U21-EN-Pad5)") (class "Default")
      (node (ref "U21") (pin "5") (pinfunction "EN_5") (pintype "unspecified+no_connect"))
    )
    (net (code "171") (name "unconnected-(U21-MODE-Pad6)") (class "Default")
      (node (ref "U21") (pin "6") (pinfunction "MODE_6") (pintype "unspecified+no_connect"))
    )
    (net (code "172") (name "unconnected-(U25-CE-Pad13)") (class "Default")
      (node (ref "U25") (pin "13") (pinfunction "CE_13") (pintype "unspecified"))
    )
    (net (code "173") (name "unconnected-(U25-INT-Pad21)") (class "Default")
      (node (ref "U25") (pin "21") (pinfunction "INT_21") (pintype "unspecified"))
    )
    (net (code "174") (name "unconnected-(U25-NC-Pad6)") (class "Default")
      (node (ref "U25") (pin "6") (pinfunction "NC_6") (pintype "unspecified+no_connect"))
    )
    (net (code "175") (name "unconnected-(U25-NC-Pad7)") (class "Default")
      (node (ref "U25") (pin "7") (pinfunction "NC_7") (pintype "unspecified+no_connect"))
    )
    (net (code "176") (name "unconnected-(U25-QON-Pad12)") (class "Default")
      (node (ref "U25") (pin "12") (pinfunction "QON_12") (pintype "unspecified"))
    )
    (net (code "177") (name "unconnected-(U25-SCL-Pad14)") (class "Default")
      (node (ref "U25") (pin "14") (pinfunction "SCL_14") (pintype "unspecified"))
    )
    (net (code "178") (name "unconnected-(U25-SDA-Pad15)") (class "Default")
      (node (ref "U25") (pin "15") (pinfunction "SDA_15") (pintype "unspecified"))
    )
    (net (code "179") (name "unconnected-(U30-MODE-Pad9)") (class "Default")
      (node (ref "U30") (pin "9") (pinfunction "MODE_9") (pintype "unspecified+no_connect"))
    )
    (net (code "180") (name "unconnected-(U30-MUTE#-Pad5)") (class "Default")
      (node (ref "U30") (pin "5") (pinfunction "MUTE#_5") (pintype "unspecified+no_connect"))
    )
    (net (code "181") (name "unconnected-(U30-VREF-Pad8)") (class "Default")
      (node (ref "U30") (pin "8") (pinfunction "VREF_8") (pintype "unspecified+no_connect"))
    )
    (net (code "182") (name "unconnected-(U33-Q7S-Pad9)") (class "Default")
      (node (ref "U33") (pin "9") (pinfunction "Q7S_9") (pintype "unspecified+no_connect"))
    )
  )
)
